# ELC102_-_Green_Digits.net
KiCad netlist of a schematic drawn in Altium Designer
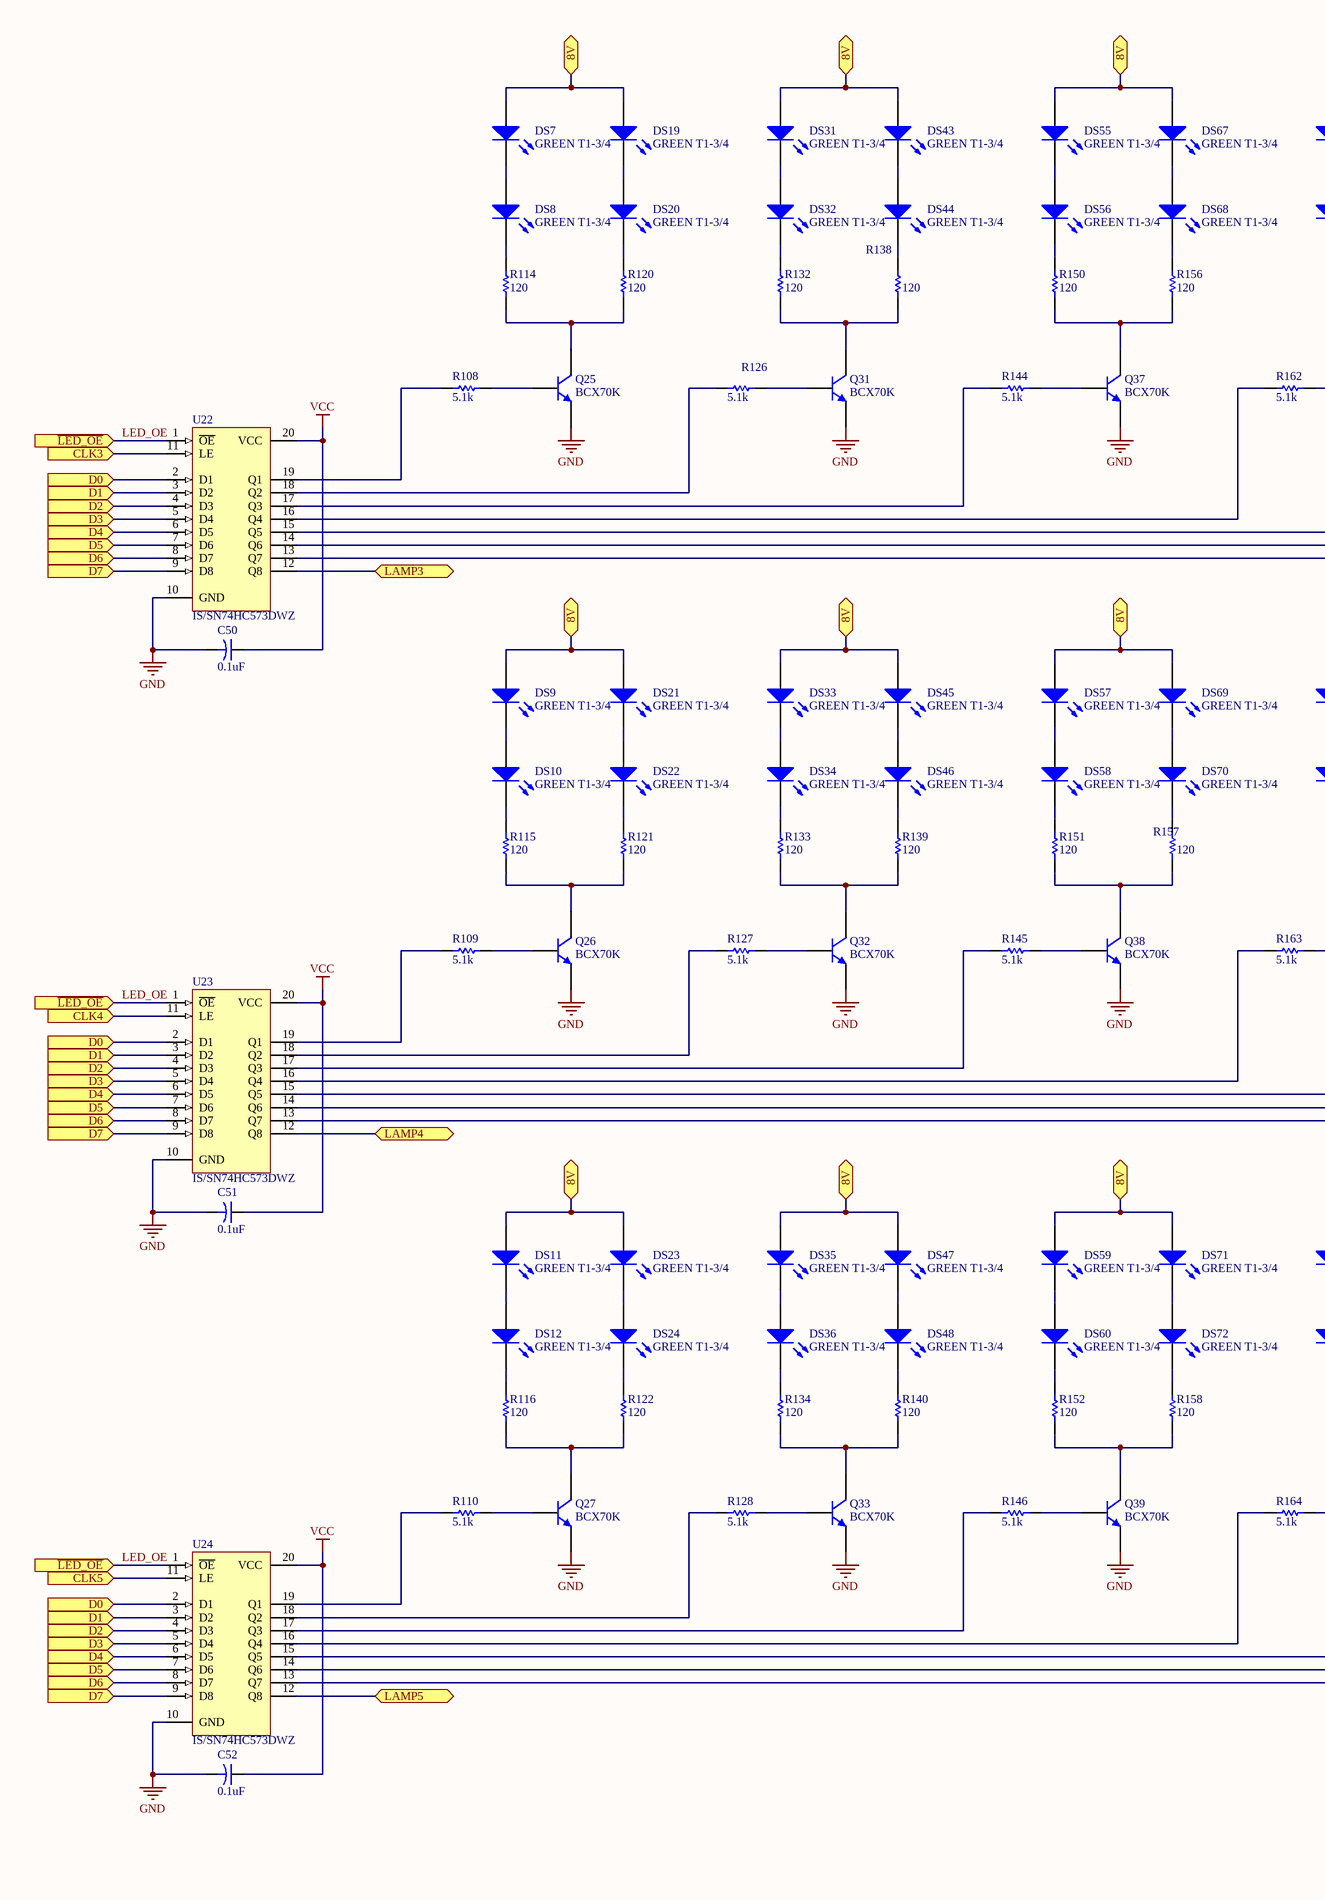
[diagram p0: ELC102 - Green Digits.SchDoc, left]
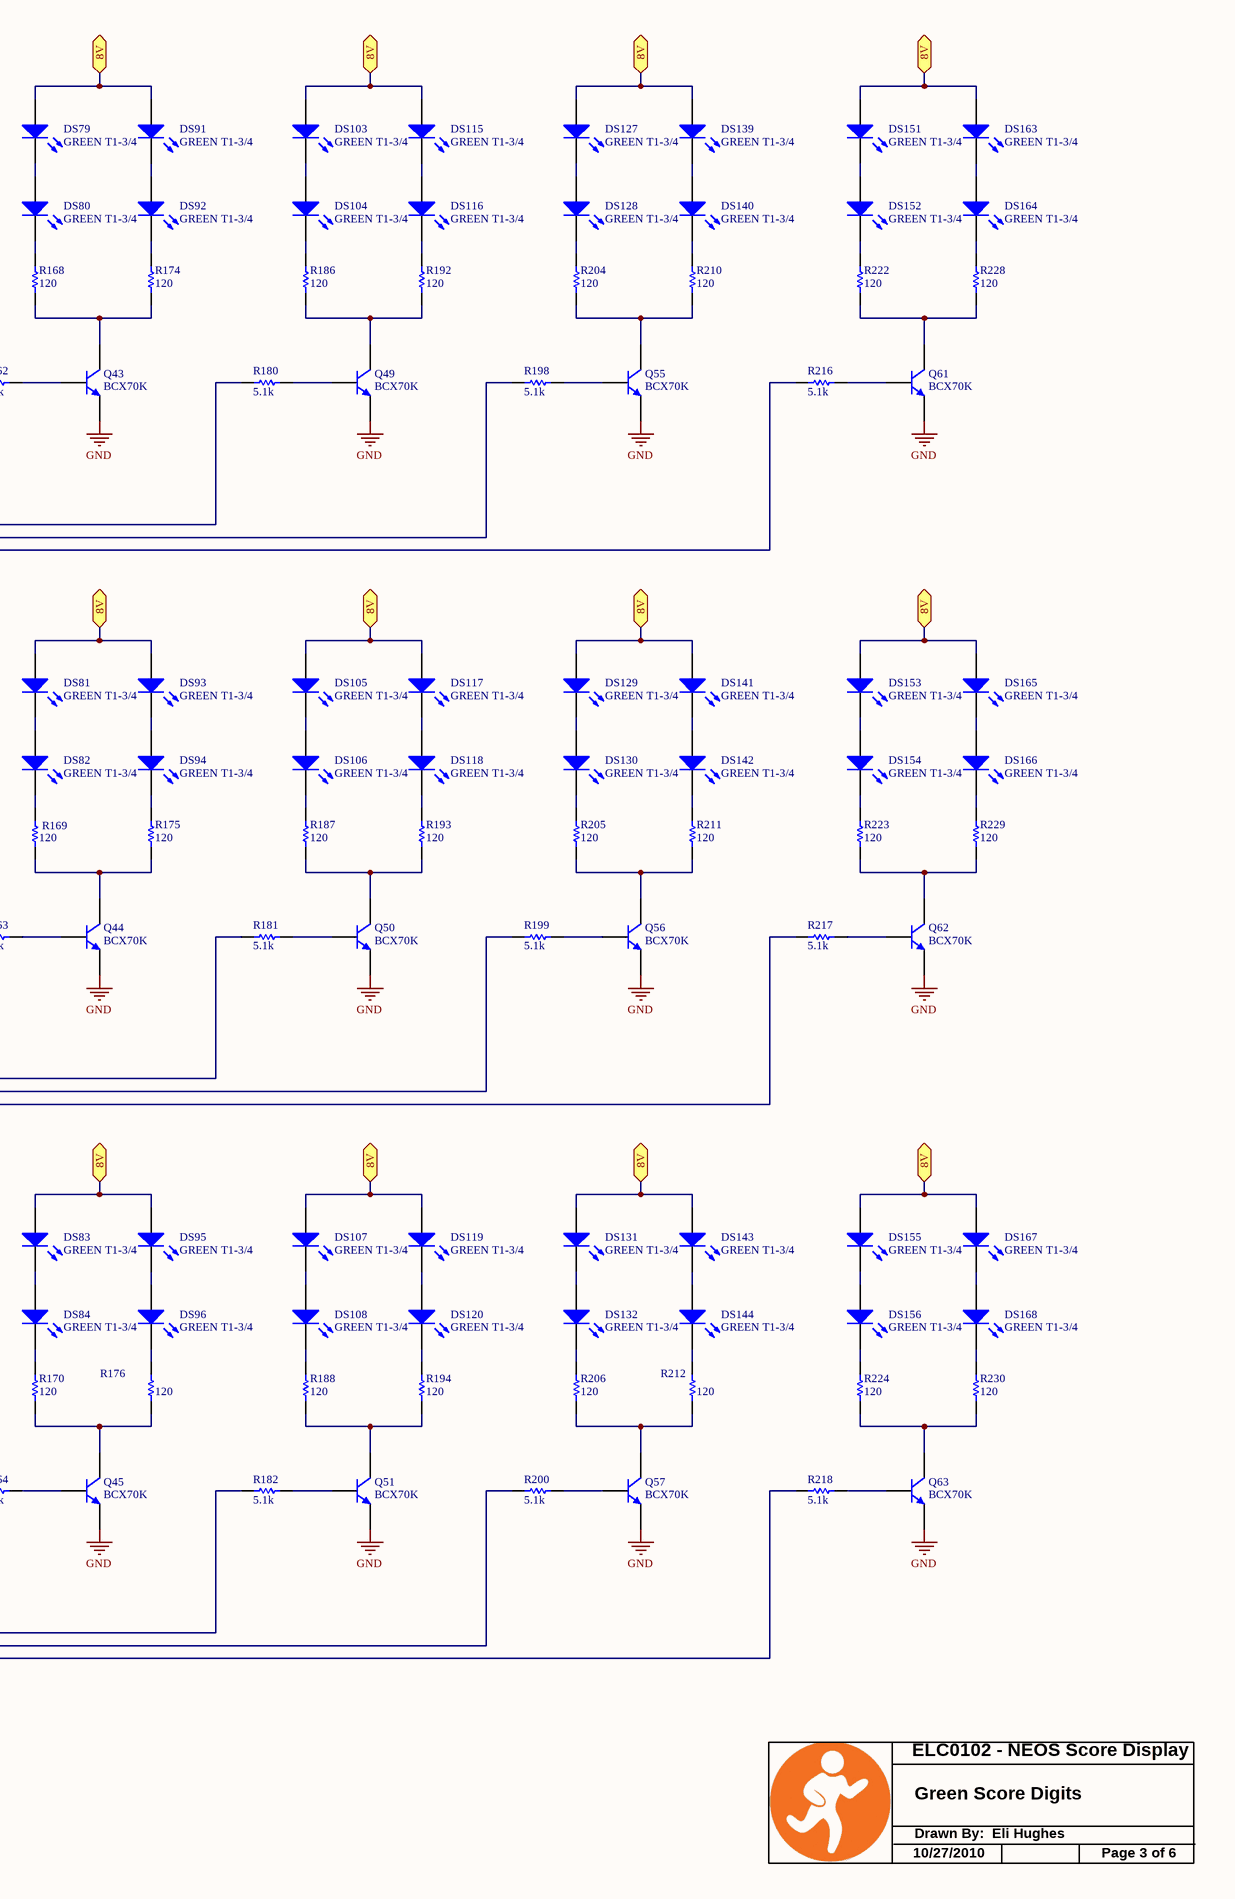
[diagram p1: ELC102 - Green Digits.SchDoc, right]

(export (version "E")
  (design (tool "Eeschema 10.0.6"))
  (components
    (comp (ref "C50")
      (value "0.1uF")
      (footprint "C0805")
      (description "CAP .10UF 50V CERAMIC X7R 0805")
      (fields
        (field (name "MANUFACTURER") "Kemet")
        (field (name "MANUFACTURER PART NUMBER") "C0805C104K5RACTU")
        (field (name "SOURCE") "Digikey")
      )
      (libsource (lib "ELC102 - Scoreboard") (part "CS/C0805C104K5RACK"))
    )
    (comp (ref "C51")
      (value "0.1uF")
      (footprint "C0805")
      (description "CAP .10UF 50V CERAMIC X7R 0805")
      (fields
        (field (name "MANUFACTURER") "Kemet")
        (field (name "MANUFACTURER PART NUMBER") "C0805C104K5RACTU")
        (field (name "SOURCE") "Digikey")
      )
      (libsource (lib "ELC102 - Scoreboard") (part "CS/C0805C104K5RACK"))
    )
    (comp (ref "C52")
      (value "0.1uF")
      (footprint "C0805")
      (description "CAP .10UF 50V CERAMIC X7R 0805")
      (fields
        (field (name "MANUFACTURER") "Kemet")
        (field (name "MANUFACTURER PART NUMBER") "C0805C104K5RACTU")
        (field (name "SOURCE") "Digikey")
      )
      (libsource (lib "ELC102 - Scoreboard") (part "CS/C0805C104K5RACK"))
    )
    (comp (ref "DS7")
      (value "GREEN T1-3/4")
      (footprint "LED T1-3/4 Flush")
      (description "Optek LED Green/Clear High Brightness T1-3/4")
      (fields
        (field (name "MANUFACTURER") "OPTEK")
        (field (name "MANUFACTURER PART NUMBER") "OVLFG3C7")
        (field (name "SOURCE") "Digikey")
      )
      (libsource (lib "ScoreBoard") (part "LGCOVLFG3C7Z"))
    )
    (comp (ref "DS8")
      (value "GREEN T1-3/4")
      (footprint "LED T1-3/4 Flush")
      (description "Optek LED Green/Clear High Brightness T1-3/4")
      (fields
        (field (name "MANUFACTURER") "OPTEK")
        (field (name "MANUFACTURER PART NUMBER") "OVLFG3C7")
        (field (name "SOURCE") "Digikey")
      )
      (libsource (lib "ScoreBoard") (part "LGCOVLFG3C7Z"))
    )
    (comp (ref "DS9")
      (value "GREEN T1-3/4")
      (footprint "LED T1-3/4 Flush")
      (description "Optek LED Green/Clear High Brightness T1-3/4")
      (fields
        (field (name "MANUFACTURER") "OPTEK")
        (field (name "MANUFACTURER PART NUMBER") "OVLFG3C7")
        (field (name "SOURCE") "Digikey")
      )
      (libsource (lib "ScoreBoard") (part "LGCOVLFG3C7Z"))
    )
    (comp (ref "DS10")
      (value "GREEN T1-3/4")
      (footprint "LED T1-3/4 Flush")
      (description "Optek LED Green/Clear High Brightness T1-3/4")
      (fields
        (field (name "MANUFACTURER") "OPTEK")
        (field (name "MANUFACTURER PART NUMBER") "OVLFG3C7")
        (field (name "SOURCE") "Digikey")
      )
      (libsource (lib "ScoreBoard") (part "LGCOVLFG3C7Z"))
    )
    (comp (ref "DS11")
      (value "GREEN T1-3/4")
      (footprint "LED T1-3/4 Flush")
      (description "Optek LED Green/Clear High Brightness T1-3/4")
      (fields
        (field (name "MANUFACTURER") "OPTEK")
        (field (name "MANUFACTURER PART NUMBER") "OVLFG3C7")
        (field (name "SOURCE") "Digikey")
      )
      (libsource (lib "ScoreBoard") (part "LGCOVLFG3C7Z"))
    )
    (comp (ref "DS12")
      (value "GREEN T1-3/4")
      (footprint "LED T1-3/4 Flush")
      (description "Optek LED Green/Clear High Brightness T1-3/4")
      (fields
        (field (name "MANUFACTURER") "OPTEK")
        (field (name "MANUFACTURER PART NUMBER") "OVLFG3C7")
        (field (name "SOURCE") "Digikey")
      )
      (libsource (lib "ScoreBoard") (part "LGCOVLFG3C7Z"))
    )
    (comp (ref "DS19")
      (value "GREEN T1-3/4")
      (footprint "LED T1-3/4 Flush")
      (description "Optek LED Green/Clear High Brightness T1-3/4")
      (fields
        (field (name "MANUFACTURER") "OPTEK")
        (field (name "MANUFACTURER PART NUMBER") "OVLFG3C7")
        (field (name "SOURCE") "Digikey")
      )
      (libsource (lib "ScoreBoard") (part "LGCOVLFG3C7Z"))
    )
    (comp (ref "DS20")
      (value "GREEN T1-3/4")
      (footprint "LED T1-3/4 Flush")
      (description "Optek LED Green/Clear High Brightness T1-3/4")
      (fields
        (field (name "MANUFACTURER") "OPTEK")
        (field (name "MANUFACTURER PART NUMBER") "OVLFG3C7")
        (field (name "SOURCE") "Digikey")
      )
      (libsource (lib "ScoreBoard") (part "LGCOVLFG3C7Z"))
    )
    (comp (ref "DS21")
      (value "GREEN T1-3/4")
      (footprint "LED T1-3/4 Flush")
      (description "Optek LED Green/Clear High Brightness T1-3/4")
      (fields
        (field (name "MANUFACTURER") "OPTEK")
        (field (name "MANUFACTURER PART NUMBER") "OVLFG3C7")
        (field (name "SOURCE") "Digikey")
      )
      (libsource (lib "ScoreBoard") (part "LGCOVLFG3C7Z"))
    )
    (comp (ref "DS22")
      (value "GREEN T1-3/4")
      (footprint "LED T1-3/4 Flush")
      (description "Optek LED Green/Clear High Brightness T1-3/4")
      (fields
        (field (name "MANUFACTURER") "OPTEK")
        (field (name "MANUFACTURER PART NUMBER") "OVLFG3C7")
        (field (name "SOURCE") "Digikey")
      )
      (libsource (lib "ScoreBoard") (part "LGCOVLFG3C7Z"))
    )
    (comp (ref "DS23")
      (value "GREEN T1-3/4")
      (footprint "LED T1-3/4 Flush")
      (description "Optek LED Green/Clear High Brightness T1-3/4")
      (fields
        (field (name "MANUFACTURER") "OPTEK")
        (field (name "MANUFACTURER PART NUMBER") "OVLFG3C7")
        (field (name "SOURCE") "Digikey")
      )
      (libsource (lib "ScoreBoard") (part "LGCOVLFG3C7Z"))
    )
    (comp (ref "DS24")
      (value "GREEN T1-3/4")
      (footprint "LED T1-3/4 Flush")
      (description "Optek LED Green/Clear High Brightness T1-3/4")
      (fields
        (field (name "MANUFACTURER") "OPTEK")
        (field (name "MANUFACTURER PART NUMBER") "OVLFG3C7")
        (field (name "SOURCE") "Digikey")
      )
      (libsource (lib "ScoreBoard") (part "LGCOVLFG3C7Z"))
    )
    (comp (ref "DS31")
      (value "GREEN T1-3/4")
      (footprint "LED T1-3/4 Flush")
      (description "Optek LED Green/Clear High Brightness T1-3/4")
      (fields
        (field (name "MANUFACTURER") "OPTEK")
        (field (name "MANUFACTURER PART NUMBER") "OVLFG3C7")
        (field (name "SOURCE") "Digikey")
      )
      (libsource (lib "ScoreBoard") (part "LGCOVLFG3C7Z"))
    )
    (comp (ref "DS32")
      (value "GREEN T1-3/4")
      (footprint "LED T1-3/4 Flush")
      (description "Optek LED Green/Clear High Brightness T1-3/4")
      (fields
        (field (name "MANUFACTURER") "OPTEK")
        (field (name "MANUFACTURER PART NUMBER") "OVLFG3C7")
        (field (name "SOURCE") "Digikey")
      )
      (libsource (lib "ScoreBoard") (part "LGCOVLFG3C7Z"))
    )
    (comp (ref "DS33")
      (value "GREEN T1-3/4")
      (footprint "LED T1-3/4 Flush")
      (description "Optek LED Green/Clear High Brightness T1-3/4")
      (fields
        (field (name "MANUFACTURER") "OPTEK")
        (field (name "MANUFACTURER PART NUMBER") "OVLFG3C7")
        (field (name "SOURCE") "Digikey")
      )
      (libsource (lib "ScoreBoard") (part "LGCOVLFG3C7Z"))
    )
    (comp (ref "DS34")
      (value "GREEN T1-3/4")
      (footprint "LED T1-3/4 Flush")
      (description "Optek LED Green/Clear High Brightness T1-3/4")
      (fields
        (field (name "MANUFACTURER") "OPTEK")
        (field (name "MANUFACTURER PART NUMBER") "OVLFG3C7")
        (field (name "SOURCE") "Digikey")
      )
      (libsource (lib "ScoreBoard") (part "LGCOVLFG3C7Z"))
    )
    (comp (ref "DS35")
      (value "GREEN T1-3/4")
      (footprint "LED T1-3/4 Flush")
      (description "Optek LED Green/Clear High Brightness T1-3/4")
      (fields
        (field (name "MANUFACTURER") "OPTEK")
        (field (name "MANUFACTURER PART NUMBER") "OVLFG3C7")
        (field (name "SOURCE") "Digikey")
      )
      (libsource (lib "ScoreBoard") (part "LGCOVLFG3C7Z"))
    )
    (comp (ref "DS36")
      (value "GREEN T1-3/4")
      (footprint "LED T1-3/4 Flush")
      (description "Optek LED Green/Clear High Brightness T1-3/4")
      (fields
        (field (name "MANUFACTURER") "OPTEK")
        (field (name "MANUFACTURER PART NUMBER") "OVLFG3C7")
        (field (name "SOURCE") "Digikey")
      )
      (libsource (lib "ScoreBoard") (part "LGCOVLFG3C7Z"))
    )
    (comp (ref "DS43")
      (value "GREEN T1-3/4")
      (footprint "LED T1-3/4 Flush")
      (description "Optek LED Green/Clear High Brightness T1-3/4")
      (fields
        (field (name "MANUFACTURER") "OPTEK")
        (field (name "MANUFACTURER PART NUMBER") "OVLFG3C7")
        (field (name "SOURCE") "Digikey")
      )
      (libsource (lib "ScoreBoard") (part "LGCOVLFG3C7Z"))
    )
    (comp (ref "DS44")
      (value "GREEN T1-3/4")
      (footprint "LED T1-3/4 Flush")
      (description "Optek LED Green/Clear High Brightness T1-3/4")
      (fields
        (field (name "MANUFACTURER") "OPTEK")
        (field (name "MANUFACTURER PART NUMBER") "OVLFG3C7")
        (field (name "SOURCE") "Digikey")
      )
      (libsource (lib "ScoreBoard") (part "LGCOVLFG3C7Z"))
    )
    (comp (ref "DS45")
      (value "GREEN T1-3/4")
      (footprint "LED T1-3/4 Flush")
      (description "Optek LED Green/Clear High Brightness T1-3/4")
      (fields
        (field (name "MANUFACTURER") "OPTEK")
        (field (name "MANUFACTURER PART NUMBER") "OVLFG3C7")
        (field (name "SOURCE") "Digikey")
      )
      (libsource (lib "ScoreBoard") (part "LGCOVLFG3C7Z"))
    )
    (comp (ref "DS46")
      (value "GREEN T1-3/4")
      (footprint "LED T1-3/4 Flush")
      (description "Optek LED Green/Clear High Brightness T1-3/4")
      (fields
        (field (name "MANUFACTURER") "OPTEK")
        (field (name "MANUFACTURER PART NUMBER") "OVLFG3C7")
        (field (name "SOURCE") "Digikey")
      )
      (libsource (lib "ScoreBoard") (part "LGCOVLFG3C7Z"))
    )
    (comp (ref "DS47")
      (value "GREEN T1-3/4")
      (footprint "LED T1-3/4 Flush")
      (description "Optek LED Green/Clear High Brightness T1-3/4")
      (fields
        (field (name "MANUFACTURER") "OPTEK")
        (field (name "MANUFACTURER PART NUMBER") "OVLFG3C7")
        (field (name "SOURCE") "Digikey")
      )
      (libsource (lib "ScoreBoard") (part "LGCOVLFG3C7Z"))
    )
    (comp (ref "DS48")
      (value "GREEN T1-3/4")
      (footprint "LED T1-3/4 Flush")
      (description "Optek LED Green/Clear High Brightness T1-3/4")
      (fields
        (field (name "MANUFACTURER") "OPTEK")
        (field (name "MANUFACTURER PART NUMBER") "OVLFG3C7")
        (field (name "SOURCE") "Digikey")
      )
      (libsource (lib "ScoreBoard") (part "LGCOVLFG3C7Z"))
    )
    (comp (ref "DS55")
      (value "GREEN T1-3/4")
      (footprint "LED T1-3/4 Flush")
      (description "Optek LED Green/Clear High Brightness T1-3/4")
      (fields
        (field (name "MANUFACTURER") "OPTEK")
        (field (name "MANUFACTURER PART NUMBER") "OVLFG3C7")
        (field (name "SOURCE") "Digikey")
      )
      (libsource (lib "ScoreBoard") (part "LGCOVLFG3C7Z"))
    )
    (comp (ref "DS56")
      (value "GREEN T1-3/4")
      (footprint "LED T1-3/4 Flush")
      (description "Optek LED Green/Clear High Brightness T1-3/4")
      (fields
        (field (name "MANUFACTURER") "OPTEK")
        (field (name "MANUFACTURER PART NUMBER") "OVLFG3C7")
        (field (name "SOURCE") "Digikey")
      )
      (libsource (lib "ScoreBoard") (part "LGCOVLFG3C7Z"))
    )
    (comp (ref "DS57")
      (value "GREEN T1-3/4")
      (footprint "LED T1-3/4 Flush")
      (description "Optek LED Green/Clear High Brightness T1-3/4")
      (fields
        (field (name "MANUFACTURER") "OPTEK")
        (field (name "MANUFACTURER PART NUMBER") "OVLFG3C7")
        (field (name "SOURCE") "Digikey")
      )
      (libsource (lib "ScoreBoard") (part "LGCOVLFG3C7Z"))
    )
    (comp (ref "DS58")
      (value "GREEN T1-3/4")
      (footprint "LED T1-3/4 Flush")
      (description "Optek LED Green/Clear High Brightness T1-3/4")
      (fields
        (field (name "MANUFACTURER") "OPTEK")
        (field (name "MANUFACTURER PART NUMBER") "OVLFG3C7")
        (field (name "SOURCE") "Digikey")
      )
      (libsource (lib "ScoreBoard") (part "LGCOVLFG3C7Z"))
    )
    (comp (ref "DS59")
      (value "GREEN T1-3/4")
      (footprint "LED T1-3/4 Flush")
      (description "Optek LED Green/Clear High Brightness T1-3/4")
      (fields
        (field (name "MANUFACTURER") "OPTEK")
        (field (name "MANUFACTURER PART NUMBER") "OVLFG3C7")
        (field (name "SOURCE") "Digikey")
      )
      (libsource (lib "ScoreBoard") (part "LGCOVLFG3C7Z"))
    )
    (comp (ref "DS60")
      (value "GREEN T1-3/4")
      (footprint "LED T1-3/4 Flush")
      (description "Optek LED Green/Clear High Brightness T1-3/4")
      (fields
        (field (name "MANUFACTURER") "OPTEK")
        (field (name "MANUFACTURER PART NUMBER") "OVLFG3C7")
        (field (name "SOURCE") "Digikey")
      )
      (libsource (lib "ScoreBoard") (part "LGCOVLFG3C7Z"))
    )
    (comp (ref "DS67")
      (value "GREEN T1-3/4")
      (footprint "LED T1-3/4 Flush")
      (description "Optek LED Green/Clear High Brightness T1-3/4")
      (fields
        (field (name "MANUFACTURER") "OPTEK")
        (field (name "MANUFACTURER PART NUMBER") "OVLFG3C7")
        (field (name "SOURCE") "Digikey")
      )
      (libsource (lib "ScoreBoard") (part "LGCOVLFG3C7Z"))
    )
    (comp (ref "DS68")
      (value "GREEN T1-3/4")
      (footprint "LED T1-3/4 Flush")
      (description "Optek LED Green/Clear High Brightness T1-3/4")
      (fields
        (field (name "MANUFACTURER") "OPTEK")
        (field (name "MANUFACTURER PART NUMBER") "OVLFG3C7")
        (field (name "SOURCE") "Digikey")
      )
      (libsource (lib "ScoreBoard") (part "LGCOVLFG3C7Z"))
    )
    (comp (ref "DS69")
      (value "GREEN T1-3/4")
      (footprint "LED T1-3/4 Flush")
      (description "Optek LED Green/Clear High Brightness T1-3/4")
      (fields
        (field (name "MANUFACTURER") "OPTEK")
        (field (name "MANUFACTURER PART NUMBER") "OVLFG3C7")
        (field (name "SOURCE") "Digikey")
      )
      (libsource (lib "ScoreBoard") (part "LGCOVLFG3C7Z"))
    )
    (comp (ref "DS70")
      (value "GREEN T1-3/4")
      (footprint "LED T1-3/4 Flush")
      (description "Optek LED Green/Clear High Brightness T1-3/4")
      (fields
        (field (name "MANUFACTURER") "OPTEK")
        (field (name "MANUFACTURER PART NUMBER") "OVLFG3C7")
        (field (name "SOURCE") "Digikey")
      )
      (libsource (lib "ScoreBoard") (part "LGCOVLFG3C7Z"))
    )
    (comp (ref "DS71")
      (value "GREEN T1-3/4")
      (footprint "LED T1-3/4 Flush")
      (description "Optek LED Green/Clear High Brightness T1-3/4")
      (fields
        (field (name "MANUFACTURER") "OPTEK")
        (field (name "MANUFACTURER PART NUMBER") "OVLFG3C7")
        (field (name "SOURCE") "Digikey")
      )
      (libsource (lib "ScoreBoard") (part "LGCOVLFG3C7Z"))
    )
    (comp (ref "DS72")
      (value "GREEN T1-3/4")
      (footprint "LED T1-3/4 Flush")
      (description "Optek LED Green/Clear High Brightness T1-3/4")
      (fields
        (field (name "MANUFACTURER") "OPTEK")
        (field (name "MANUFACTURER PART NUMBER") "OVLFG3C7")
        (field (name "SOURCE") "Digikey")
      )
      (libsource (lib "ScoreBoard") (part "LGCOVLFG3C7Z"))
    )
    (comp (ref "DS79")
      (value "GREEN T1-3/4")
      (footprint "LED T1-3/4 Flush")
      (description "Optek LED Green/Clear High Brightness T1-3/4")
      (fields
        (field (name "MANUFACTURER") "OPTEK")
        (field (name "MANUFACTURER PART NUMBER") "OVLFG3C7")
        (field (name "SOURCE") "Digikey")
      )
      (libsource (lib "ScoreBoard") (part "LGCOVLFG3C7Z"))
    )
    (comp (ref "DS80")
      (value "GREEN T1-3/4")
      (footprint "LED T1-3/4 Flush")
      (description "Optek LED Green/Clear High Brightness T1-3/4")
      (fields
        (field (name "MANUFACTURER") "OPTEK")
        (field (name "MANUFACTURER PART NUMBER") "OVLFG3C7")
        (field (name "SOURCE") "Digikey")
      )
      (libsource (lib "ScoreBoard") (part "LGCOVLFG3C7Z"))
    )
    (comp (ref "DS81")
      (value "GREEN T1-3/4")
      (footprint "LED T1-3/4 Flush")
      (description "Optek LED Green/Clear High Brightness T1-3/4")
      (fields
        (field (name "MANUFACTURER") "OPTEK")
        (field (name "MANUFACTURER PART NUMBER") "OVLFG3C7")
        (field (name "SOURCE") "Digikey")
      )
      (libsource (lib "ScoreBoard") (part "LGCOVLFG3C7Z"))
    )
    (comp (ref "DS82")
      (value "GREEN T1-3/4")
      (footprint "LED T1-3/4 Flush")
      (description "Optek LED Green/Clear High Brightness T1-3/4")
      (fields
        (field (name "MANUFACTURER") "OPTEK")
        (field (name "MANUFACTURER PART NUMBER") "OVLFG3C7")
        (field (name "SOURCE") "Digikey")
      )
      (libsource (lib "ScoreBoard") (part "LGCOVLFG3C7Z"))
    )
    (comp (ref "DS83")
      (value "GREEN T1-3/4")
      (footprint "LED T1-3/4 Flush")
      (description "Optek LED Green/Clear High Brightness T1-3/4")
      (fields
        (field (name "MANUFACTURER") "OPTEK")
        (field (name "MANUFACTURER PART NUMBER") "OVLFG3C7")
        (field (name "SOURCE") "Digikey")
      )
      (libsource (lib "ScoreBoard") (part "LGCOVLFG3C7Z"))
    )
    (comp (ref "DS84")
      (value "GREEN T1-3/4")
      (footprint "LED T1-3/4 Flush")
      (description "Optek LED Green/Clear High Brightness T1-3/4")
      (fields
        (field (name "MANUFACTURER") "OPTEK")
        (field (name "MANUFACTURER PART NUMBER") "OVLFG3C7")
        (field (name "SOURCE") "Digikey")
      )
      (libsource (lib "ScoreBoard") (part "LGCOVLFG3C7Z"))
    )
    (comp (ref "DS91")
      (value "GREEN T1-3/4")
      (footprint "LED T1-3/4 Flush")
      (description "Optek LED Green/Clear High Brightness T1-3/4")
      (fields
        (field (name "MANUFACTURER") "OPTEK")
        (field (name "MANUFACTURER PART NUMBER") "OVLFG3C7")
        (field (name "SOURCE") "Digikey")
      )
      (libsource (lib "ScoreBoard") (part "LGCOVLFG3C7Z"))
    )
    (comp (ref "DS92")
      (value "GREEN T1-3/4")
      (footprint "LED T1-3/4 Flush")
      (description "Optek LED Green/Clear High Brightness T1-3/4")
      (fields
        (field (name "MANUFACTURER") "OPTEK")
        (field (name "MANUFACTURER PART NUMBER") "OVLFG3C7")
        (field (name "SOURCE") "Digikey")
      )
      (libsource (lib "ScoreBoard") (part "LGCOVLFG3C7Z"))
    )
    (comp (ref "DS93")
      (value "GREEN T1-3/4")
      (footprint "LED T1-3/4 Flush")
      (description "Optek LED Green/Clear High Brightness T1-3/4")
      (fields
        (field (name "MANUFACTURER") "OPTEK")
        (field (name "MANUFACTURER PART NUMBER") "OVLFG3C7")
        (field (name "SOURCE") "Digikey")
      )
      (libsource (lib "ScoreBoard") (part "LGCOVLFG3C7Z"))
    )
    (comp (ref "DS94")
      (value "GREEN T1-3/4")
      (footprint "LED T1-3/4 Flush")
      (description "Optek LED Green/Clear High Brightness T1-3/4")
      (fields
        (field (name "MANUFACTURER") "OPTEK")
        (field (name "MANUFACTURER PART NUMBER") "OVLFG3C7")
        (field (name "SOURCE") "Digikey")
      )
      (libsource (lib "ScoreBoard") (part "LGCOVLFG3C7Z"))
    )
    (comp (ref "DS95")
      (value "GREEN T1-3/4")
      (footprint "LED T1-3/4 Flush")
      (description "Optek LED Green/Clear High Brightness T1-3/4")
      (fields
        (field (name "MANUFACTURER") "OPTEK")
        (field (name "MANUFACTURER PART NUMBER") "OVLFG3C7")
        (field (name "SOURCE") "Digikey")
      )
      (libsource (lib "ScoreBoard") (part "LGCOVLFG3C7Z"))
    )
    (comp (ref "DS96")
      (value "GREEN T1-3/4")
      (footprint "LED T1-3/4 Flush")
      (description "Optek LED Green/Clear High Brightness T1-3/4")
      (fields
        (field (name "MANUFACTURER") "OPTEK")
        (field (name "MANUFACTURER PART NUMBER") "OVLFG3C7")
        (field (name "SOURCE") "Digikey")
      )
      (libsource (lib "ScoreBoard") (part "LGCOVLFG3C7Z"))
    )
    (comp (ref "DS103")
      (value "GREEN T1-3/4")
      (footprint "LED T1-3/4 Flush")
      (description "Optek LED Green/Clear High Brightness T1-3/4")
      (fields
        (field (name "MANUFACTURER") "OPTEK")
        (field (name "MANUFACTURER PART NUMBER") "OVLFG3C7")
        (field (name "SOURCE") "Digikey")
      )
      (libsource (lib "ScoreBoard") (part "LGCOVLFG3C7Z"))
    )
    (comp (ref "DS104")
      (value "GREEN T1-3/4")
      (footprint "LED T1-3/4 Flush")
      (description "Optek LED Green/Clear High Brightness T1-3/4")
      (fields
        (field (name "MANUFACTURER") "OPTEK")
        (field (name "MANUFACTURER PART NUMBER") "OVLFG3C7")
        (field (name "SOURCE") "Digikey")
      )
      (libsource (lib "ScoreBoard") (part "LGCOVLFG3C7Z"))
    )
    (comp (ref "DS105")
      (value "GREEN T1-3/4")
      (footprint "LED T1-3/4 Flush")
      (description "Optek LED Green/Clear High Brightness T1-3/4")
      (fields
        (field (name "MANUFACTURER") "OPTEK")
        (field (name "MANUFACTURER PART NUMBER") "OVLFG3C7")
        (field (name "SOURCE") "Digikey")
      )
      (libsource (lib "ScoreBoard") (part "LGCOVLFG3C7Z"))
    )
    (comp (ref "DS106")
      (value "GREEN T1-3/4")
      (footprint "LED T1-3/4 Flush")
      (description "Optek LED Green/Clear High Brightness T1-3/4")
      (fields
        (field (name "MANUFACTURER") "OPTEK")
        (field (name "MANUFACTURER PART NUMBER") "OVLFG3C7")
        (field (name "SOURCE") "Digikey")
      )
      (libsource (lib "ScoreBoard") (part "LGCOVLFG3C7Z"))
    )
    (comp (ref "DS107")
      (value "GREEN T1-3/4")
      (footprint "LED T1-3/4 Flush")
      (description "Optek LED Green/Clear High Brightness T1-3/4")
      (fields
        (field (name "MANUFACTURER") "OPTEK")
        (field (name "MANUFACTURER PART NUMBER") "OVLFG3C7")
        (field (name "SOURCE") "Digikey")
      )
      (libsource (lib "ScoreBoard") (part "LGCOVLFG3C7Z"))
    )
    (comp (ref "DS108")
      (value "GREEN T1-3/4")
      (footprint "LED T1-3/4 Flush")
      (description "Optek LED Green/Clear High Brightness T1-3/4")
      (fields
        (field (name "MANUFACTURER") "OPTEK")
        (field (name "MANUFACTURER PART NUMBER") "OVLFG3C7")
        (field (name "SOURCE") "Digikey")
      )
      (libsource (lib "ScoreBoard") (part "LGCOVLFG3C7Z"))
    )
    (comp (ref "DS115")
      (value "GREEN T1-3/4")
      (footprint "LED T1-3/4 Flush")
      (description "Optek LED Green/Clear High Brightness T1-3/4")
      (fields
        (field (name "MANUFACTURER") "OPTEK")
        (field (name "MANUFACTURER PART NUMBER") "OVLFG3C7")
        (field (name "SOURCE") "Digikey")
      )
      (libsource (lib "ScoreBoard") (part "LGCOVLFG3C7Z"))
    )
    (comp (ref "DS116")
      (value "GREEN T1-3/4")
      (footprint "LED T1-3/4 Flush")
      (description "Optek LED Green/Clear High Brightness T1-3/4")
      (fields
        (field (name "MANUFACTURER") "OPTEK")
        (field (name "MANUFACTURER PART NUMBER") "OVLFG3C7")
        (field (name "SOURCE") "Digikey")
      )
      (libsource (lib "ScoreBoard") (part "LGCOVLFG3C7Z"))
    )
    (comp (ref "DS117")
      (value "GREEN T1-3/4")
      (footprint "LED T1-3/4 Flush")
      (description "Optek LED Green/Clear High Brightness T1-3/4")
      (fields
        (field (name "MANUFACTURER") "OPTEK")
        (field (name "MANUFACTURER PART NUMBER") "OVLFG3C7")
        (field (name "SOURCE") "Digikey")
      )
      (libsource (lib "ScoreBoard") (part "LGCOVLFG3C7Z"))
    )
    (comp (ref "DS118")
      (value "GREEN T1-3/4")
      (footprint "LED T1-3/4 Flush")
      (description "Optek LED Green/Clear High Brightness T1-3/4")
      (fields
        (field (name "MANUFACTURER") "OPTEK")
        (field (name "MANUFACTURER PART NUMBER") "OVLFG3C7")
        (field (name "SOURCE") "Digikey")
      )
      (libsource (lib "ScoreBoard") (part "LGCOVLFG3C7Z"))
    )
    (comp (ref "DS119")
      (value "GREEN T1-3/4")
      (footprint "LED T1-3/4 Flush")
      (description "Optek LED Green/Clear High Brightness T1-3/4")
      (fields
        (field (name "MANUFACTURER") "OPTEK")
        (field (name "MANUFACTURER PART NUMBER") "OVLFG3C7")
        (field (name "SOURCE") "Digikey")
      )
      (libsource (lib "ScoreBoard") (part "LGCOVLFG3C7Z"))
    )
    (comp (ref "DS120")
      (value "GREEN T1-3/4")
      (footprint "LED T1-3/4 Flush")
      (description "Optek LED Green/Clear High Brightness T1-3/4")
      (fields
        (field (name "MANUFACTURER") "OPTEK")
        (field (name "MANUFACTURER PART NUMBER") "OVLFG3C7")
        (field (name "SOURCE") "Digikey")
      )
      (libsource (lib "ScoreBoard") (part "LGCOVLFG3C7Z"))
    )
    (comp (ref "DS127")
      (value "GREEN T1-3/4")
      (footprint "LED T1-3/4 Flush")
      (description "Optek LED Green/Clear High Brightness T1-3/4")
      (fields
        (field (name "MANUFACTURER") "OPTEK")
        (field (name "MANUFACTURER PART NUMBER") "OVLFG3C7")
        (field (name "SOURCE") "Digikey")
      )
      (libsource (lib "ScoreBoard") (part "LGCOVLFG3C7Z"))
    )
    (comp (ref "DS128")
      (value "GREEN T1-3/4")
      (footprint "LED T1-3/4 Flush")
      (description "Optek LED Green/Clear High Brightness T1-3/4")
      (fields
        (field (name "MANUFACTURER") "OPTEK")
        (field (name "MANUFACTURER PART NUMBER") "OVLFG3C7")
        (field (name "SOURCE") "Digikey")
      )
      (libsource (lib "ScoreBoard") (part "LGCOVLFG3C7Z"))
    )
    (comp (ref "DS129")
      (value "GREEN T1-3/4")
      (footprint "LED T1-3/4 Flush")
      (description "Optek LED Green/Clear High Brightness T1-3/4")
      (fields
        (field (name "MANUFACTURER") "OPTEK")
        (field (name "MANUFACTURER PART NUMBER") "OVLFG3C7")
        (field (name "SOURCE") "Digikey")
      )
      (libsource (lib "ScoreBoard") (part "LGCOVLFG3C7Z"))
    )
    (comp (ref "DS130")
      (value "GREEN T1-3/4")
      (footprint "LED T1-3/4 Flush")
      (description "Optek LED Green/Clear High Brightness T1-3/4")
      (fields
        (field (name "MANUFACTURER") "OPTEK")
        (field (name "MANUFACTURER PART NUMBER") "OVLFG3C7")
        (field (name "SOURCE") "Digikey")
      )
      (libsource (lib "ScoreBoard") (part "LGCOVLFG3C7Z"))
    )
    (comp (ref "DS131")
      (value "GREEN T1-3/4")
      (footprint "LED T1-3/4 Flush")
      (description "Optek LED Green/Clear High Brightness T1-3/4")
      (fields
        (field (name "MANUFACTURER") "OPTEK")
        (field (name "MANUFACTURER PART NUMBER") "OVLFG3C7")
        (field (name "SOURCE") "Digikey")
      )
      (libsource (lib "ScoreBoard") (part "LGCOVLFG3C7Z"))
    )
    (comp (ref "DS132")
      (value "GREEN T1-3/4")
      (footprint "LED T1-3/4 Flush")
      (description "Optek LED Green/Clear High Brightness T1-3/4")
      (fields
        (field (name "MANUFACTURER") "OPTEK")
        (field (name "MANUFACTURER PART NUMBER") "OVLFG3C7")
        (field (name "SOURCE") "Digikey")
      )
      (libsource (lib "ScoreBoard") (part "LGCOVLFG3C7Z"))
    )
    (comp (ref "DS139")
      (value "GREEN T1-3/4")
      (footprint "LED T1-3/4 Flush")
      (description "Optek LED Green/Clear High Brightness T1-3/4")
      (fields
        (field (name "MANUFACTURER") "OPTEK")
        (field (name "MANUFACTURER PART NUMBER") "OVLFG3C7")
        (field (name "SOURCE") "Digikey")
      )
      (libsource (lib "ScoreBoard") (part "LGCOVLFG3C7Z"))
    )
    (comp (ref "DS140")
      (value "GREEN T1-3/4")
      (footprint "LED T1-3/4 Flush")
      (description "Optek LED Green/Clear High Brightness T1-3/4")
      (fields
        (field (name "MANUFACTURER") "OPTEK")
        (field (name "MANUFACTURER PART NUMBER") "OVLFG3C7")
        (field (name "SOURCE") "Digikey")
      )
      (libsource (lib "ScoreBoard") (part "LGCOVLFG3C7Z"))
    )
    (comp (ref "DS141")
      (value "GREEN T1-3/4")
      (footprint "LED T1-3/4 Flush")
      (description "Optek LED Green/Clear High Brightness T1-3/4")
      (fields
        (field (name "MANUFACTURER") "OPTEK")
        (field (name "MANUFACTURER PART NUMBER") "OVLFG3C7")
        (field (name "SOURCE") "Digikey")
      )
      (libsource (lib "ScoreBoard") (part "LGCOVLFG3C7Z"))
    )
    (comp (ref "DS142")
      (value "GREEN T1-3/4")
      (footprint "LED T1-3/4 Flush")
      (description "Optek LED Green/Clear High Brightness T1-3/4")
      (fields
        (field (name "MANUFACTURER") "OPTEK")
        (field (name "MANUFACTURER PART NUMBER") "OVLFG3C7")
        (field (name "SOURCE") "Digikey")
      )
      (libsource (lib "ScoreBoard") (part "LGCOVLFG3C7Z"))
    )
    (comp (ref "DS143")
      (value "GREEN T1-3/4")
      (footprint "LED T1-3/4 Flush")
      (description "Optek LED Green/Clear High Brightness T1-3/4")
      (fields
        (field (name "MANUFACTURER") "OPTEK")
        (field (name "MANUFACTURER PART NUMBER") "OVLFG3C7")
        (field (name "SOURCE") "Digikey")
      )
      (libsource (lib "ScoreBoard") (part "LGCOVLFG3C7Z"))
    )
    (comp (ref "DS144")
      (value "GREEN T1-3/4")
      (footprint "LED T1-3/4 Flush")
      (description "Optek LED Green/Clear High Brightness T1-3/4")
      (fields
        (field (name "MANUFACTURER") "OPTEK")
        (field (name "MANUFACTURER PART NUMBER") "OVLFG3C7")
        (field (name "SOURCE") "Digikey")
      )
      (libsource (lib "ScoreBoard") (part "LGCOVLFG3C7Z"))
    )
    (comp (ref "DS151")
      (value "GREEN T1-3/4")
      (footprint "LED T1-3/4 Flush")
      (description "Optek LED Green/Clear High Brightness T1-3/4")
      (fields
        (field (name "MANUFACTURER") "OPTEK")
        (field (name "MANUFACTURER PART NUMBER") "OVLFG3C7")
        (field (name "SOURCE") "Digikey")
      )
      (libsource (lib "ScoreBoard") (part "LGCOVLFG3C7Z"))
    )
    (comp (ref "DS152")
      (value "GREEN T1-3/4")
      (footprint "LED T1-3/4 Flush")
      (description "Optek LED Green/Clear High Brightness T1-3/4")
      (fields
        (field (name "MANUFACTURER") "OPTEK")
        (field (name "MANUFACTURER PART NUMBER") "OVLFG3C7")
        (field (name "SOURCE") "Digikey")
      )
      (libsource (lib "ScoreBoard") (part "LGCOVLFG3C7Z"))
    )
    (comp (ref "DS153")
      (value "GREEN T1-3/4")
      (footprint "LED T1-3/4 Flush")
      (description "Optek LED Green/Clear High Brightness T1-3/4")
      (fields
        (field (name "MANUFACTURER") "OPTEK")
        (field (name "MANUFACTURER PART NUMBER") "OVLFG3C7")
        (field (name "SOURCE") "Digikey")
      )
      (libsource (lib "ScoreBoard") (part "LGCOVLFG3C7Z"))
    )
    (comp (ref "DS154")
      (value "GREEN T1-3/4")
      (footprint "LED T1-3/4 Flush")
      (description "Optek LED Green/Clear High Brightness T1-3/4")
      (fields
        (field (name "MANUFACTURER") "OPTEK")
        (field (name "MANUFACTURER PART NUMBER") "OVLFG3C7")
        (field (name "SOURCE") "Digikey")
      )
      (libsource (lib "ScoreBoard") (part "LGCOVLFG3C7Z"))
    )
    (comp (ref "DS155")
      (value "GREEN T1-3/4")
      (footprint "LED T1-3/4 Flush")
      (description "Optek LED Green/Clear High Brightness T1-3/4")
      (fields
        (field (name "MANUFACTURER") "OPTEK")
        (field (name "MANUFACTURER PART NUMBER") "OVLFG3C7")
        (field (name "SOURCE") "Digikey")
      )
      (libsource (lib "ScoreBoard") (part "LGCOVLFG3C7Z"))
    )
    (comp (ref "DS156")
      (value "GREEN T1-3/4")
      (footprint "LED T1-3/4 Flush")
      (description "Optek LED Green/Clear High Brightness T1-3/4")
      (fields
        (field (name "MANUFACTURER") "OPTEK")
        (field (name "MANUFACTURER PART NUMBER") "OVLFG3C7")
        (field (name "SOURCE") "Digikey")
      )
      (libsource (lib "ScoreBoard") (part "LGCOVLFG3C7Z"))
    )
    (comp (ref "DS163")
      (value "GREEN T1-3/4")
      (footprint "LED T1-3/4 Flush")
      (description "Optek LED Green/Clear High Brightness T1-3/4")
      (fields
        (field (name "MANUFACTURER") "OPTEK")
        (field (name "MANUFACTURER PART NUMBER") "OVLFG3C7")
        (field (name "SOURCE") "Digikey")
      )
      (libsource (lib "ScoreBoard") (part "LGCOVLFG3C7Z"))
    )
    (comp (ref "DS164")
      (value "GREEN T1-3/4")
      (footprint "LED T1-3/4 Flush")
      (description "Optek LED Green/Clear High Brightness T1-3/4")
      (fields
        (field (name "MANUFACTURER") "OPTEK")
        (field (name "MANUFACTURER PART NUMBER") "OVLFG3C7")
        (field (name "SOURCE") "Digikey")
      )
      (libsource (lib "ScoreBoard") (part "LGCOVLFG3C7Z"))
    )
    (comp (ref "DS165")
      (value "GREEN T1-3/4")
      (footprint "LED T1-3/4 Flush")
      (description "Optek LED Green/Clear High Brightness T1-3/4")
      (fields
        (field (name "MANUFACTURER") "OPTEK")
        (field (name "MANUFACTURER PART NUMBER") "OVLFG3C7")
        (field (name "SOURCE") "Digikey")
      )
      (libsource (lib "ScoreBoard") (part "LGCOVLFG3C7Z"))
    )
    (comp (ref "DS166")
      (value "GREEN T1-3/4")
      (footprint "LED T1-3/4 Flush")
      (description "Optek LED Green/Clear High Brightness T1-3/4")
      (fields
        (field (name "MANUFACTURER") "OPTEK")
        (field (name "MANUFACTURER PART NUMBER") "OVLFG3C7")
        (field (name "SOURCE") "Digikey")
      )
      (libsource (lib "ScoreBoard") (part "LGCOVLFG3C7Z"))
    )
    (comp (ref "DS167")
      (value "GREEN T1-3/4")
      (footprint "LED T1-3/4 Flush")
      (description "Optek LED Green/Clear High Brightness T1-3/4")
      (fields
        (field (name "MANUFACTURER") "OPTEK")
        (field (name "MANUFACTURER PART NUMBER") "OVLFG3C7")
        (field (name "SOURCE") "Digikey")
      )
      (libsource (lib "ScoreBoard") (part "LGCOVLFG3C7Z"))
    )
    (comp (ref "DS168")
      (value "GREEN T1-3/4")
      (footprint "LED T1-3/4 Flush")
      (description "Optek LED Green/Clear High Brightness T1-3/4")
      (fields
        (field (name "MANUFACTURER") "OPTEK")
        (field (name "MANUFACTURER PART NUMBER") "OVLFG3C7")
        (field (name "SOURCE") "Digikey")
      )
      (libsource (lib "ScoreBoard") (part "LGCOVLFG3C7Z"))
    )
    (comp (ref "Q25")
      (value "BCX70K")
      (footprint "SOT23")
      (description "TRANS NPN AF 45V SOT-23")
      (fields (field (name "MANUFACTURER") "Fairchild Semiconductor") (field (name "SOURCE") "Digikey"))
      (libsource (lib "ScoreBoard") (part "QS/BCX70K00Z"))
    )
    (comp (ref "Q26")
      (value "BCX70K")
      (footprint "SOT23")
      (description "TRANS NPN AF 45V SOT-23")
      (fields (field (name "MANUFACTURER") "Fairchild Semiconductor") (field (name "SOURCE") "Digikey"))
      (libsource (lib "ScoreBoard") (part "QS/BCX70K00Z"))
    )
    (comp (ref "Q27")
      (value "BCX70K")
      (footprint "SOT23")
      (description "TRANS NPN AF 45V SOT-23")
      (fields (field (name "MANUFACTURER") "Fairchild Semiconductor") (field (name "SOURCE") "Digikey"))
      (libsource (lib "ScoreBoard") (part "QS/BCX70K00Z"))
    )
    (comp (ref "Q31")
      (value "BCX70K")
      (footprint "SOT23")
      (description "TRANS NPN AF 45V SOT-23")
      (fields (field (name "MANUFACTURER") "Fairchild Semiconductor") (field (name "SOURCE") "Digikey"))
      (libsource (lib "ScoreBoard") (part "QS/BCX70K00Z"))
    )
    (comp (ref "Q32")
      (value "BCX70K")
      (footprint "SOT23")
      (description "TRANS NPN AF 45V SOT-23")
      (fields (field (name "MANUFACTURER") "Fairchild Semiconductor") (field (name "SOURCE") "Digikey"))
      (libsource (lib "ScoreBoard") (part "QS/BCX70K00Z"))
    )
    (comp (ref "Q33")
      (value "BCX70K")
      (footprint "SOT23")
      (description "TRANS NPN AF 45V SOT-23")
      (fields (field (name "MANUFACTURER") "Fairchild Semiconductor") (field (name "SOURCE") "Digikey"))
      (libsource (lib "ScoreBoard") (part "QS/BCX70K00Z"))
    )
    (comp (ref "Q37")
      (value "BCX70K")
      (footprint "SOT23")
      (description "TRANS NPN AF 45V SOT-23")
      (fields (field (name "MANUFACTURER") "Fairchild Semiconductor") (field (name "SOURCE") "Digikey"))
      (libsource (lib "ScoreBoard") (part "QS/BCX70K00Z"))
    )
    (comp (ref "Q38")
      (value "BCX70K")
      (footprint "SOT23")
      (description "TRANS NPN AF 45V SOT-23")
      (fields (field (name "MANUFACTURER") "Fairchild Semiconductor") (field (name "SOURCE") "Digikey"))
      (libsource (lib "ScoreBoard") (part "QS/BCX70K00Z"))
    )
    (comp (ref "Q39")
      (value "BCX70K")
      (footprint "SOT23")
      (description "TRANS NPN AF 45V SOT-23")
      (fields (field (name "MANUFACTURER") "Fairchild Semiconductor") (field (name "SOURCE") "Digikey"))
      (libsource (lib "ScoreBoard") (part "QS/BCX70K00Z"))
    )
    (comp (ref "Q43")
      (value "BCX70K")
      (footprint "SOT23")
      (description "TRANS NPN AF 45V SOT-23")
      (fields (field (name "MANUFACTURER") "Fairchild Semiconductor") (field (name "SOURCE") "Digikey"))
      (libsource (lib "ScoreBoard") (part "QS/BCX70K00Z"))
    )
    (comp (ref "Q44")
      (value "BCX70K")
      (footprint "SOT23")
      (description "TRANS NPN AF 45V SOT-23")
      (fields (field (name "MANUFACTURER") "Fairchild Semiconductor") (field (name "SOURCE") "Digikey"))
      (libsource (lib "ScoreBoard") (part "QS/BCX70K00Z"))
    )
    (comp (ref "Q45")
      (value "BCX70K")
      (footprint "SOT23")
      (description "TRANS NPN AF 45V SOT-23")
      (fields (field (name "MANUFACTURER") "Fairchild Semiconductor") (field (name "SOURCE") "Digikey"))
      (libsource (lib "ScoreBoard") (part "QS/BCX70K00Z"))
    )
    (comp (ref "Q49")
      (value "BCX70K")
      (footprint "SOT23")
      (description "TRANS NPN AF 45V SOT-23")
      (fields (field (name "MANUFACTURER") "Fairchild Semiconductor") (field (name "SOURCE") "Digikey"))
      (libsource (lib "ScoreBoard") (part "QS/BCX70K00Z"))
    )
    (comp (ref "Q50")
      (value "BCX70K")
      (footprint "SOT23")
      (description "TRANS NPN AF 45V SOT-23")
      (fields (field (name "MANUFACTURER") "Fairchild Semiconductor") (field (name "SOURCE") "Digikey"))
      (libsource (lib "ScoreBoard") (part "QS/BCX70K00Z"))
    )
    (comp (ref "Q51")
      (value "BCX70K")
      (footprint "SOT23")
      (description "TRANS NPN AF 45V SOT-23")
      (fields (field (name "MANUFACTURER") "Fairchild Semiconductor") (field (name "SOURCE") "Digikey"))
      (libsource (lib "ScoreBoard") (part "QS/BCX70K00Z"))
    )
    (comp (ref "Q55")
      (value "BCX70K")
      (footprint "SOT23")
      (description "TRANS NPN AF 45V SOT-23")
      (fields (field (name "MANUFACTURER") "Fairchild Semiconductor") (field (name "SOURCE") "Digikey"))
      (libsource (lib "ScoreBoard") (part "QS/BCX70K00Z"))
    )
    (comp (ref "Q56")
      (value "BCX70K")
      (footprint "SOT23")
      (description "TRANS NPN AF 45V SOT-23")
      (fields (field (name "MANUFACTURER") "Fairchild Semiconductor") (field (name "SOURCE") "Digikey"))
      (libsource (lib "ScoreBoard") (part "QS/BCX70K00Z"))
    )
    (comp (ref "Q57")
      (value "BCX70K")
      (footprint "SOT23")
      (description "TRANS NPN AF 45V SOT-23")
      (fields (field (name "MANUFACTURER") "Fairchild Semiconductor") (field (name "SOURCE") "Digikey"))
      (libsource (lib "ScoreBoard") (part "QS/BCX70K00Z"))
    )
    (comp (ref "Q61")
      (value "BCX70K")
      (footprint "SOT23")
      (description "TRANS NPN AF 45V SOT-23")
      (fields (field (name "MANUFACTURER") "Fairchild Semiconductor") (field (name "SOURCE") "Digikey"))
      (libsource (lib "ScoreBoard") (part "QS/BCX70K00Z"))
    )
    (comp (ref "Q62")
      (value "BCX70K")
      (footprint "SOT23")
      (description "TRANS NPN AF 45V SOT-23")
      (fields (field (name "MANUFACTURER") "Fairchild Semiconductor") (field (name "SOURCE") "Digikey"))
      (libsource (lib "ScoreBoard") (part "QS/BCX70K00Z"))
    )
    (comp (ref "Q63")
      (value "BCX70K")
      (footprint "SOT23")
      (description "TRANS NPN AF 45V SOT-23")
      (fields (field (name "MANUFACTURER") "Fairchild Semiconductor") (field (name "SOURCE") "Digikey"))
      (libsource (lib "ScoreBoard") (part "QS/BCX70K00Z"))
    )
    (comp (ref "R108")
      (value "5.1k")
      (footprint "R0805")
      (description "RES 5.10K OHM 1/8W 1% 0805 SMD")
      (fields
        (field (name "MANUFACTURER") "Panasonic - ECG")
        (field (name "MANUFACTURER PART NUMBER") "ERJ-6ENF5101V")
      )
      (libsource (lib "eRCL") (part "ERJ-6ENF5101V"))
    )
    (comp (ref "R109")
      (value "5.1k")
      (footprint "R0805")
      (description "RES 5.10K OHM 1/8W 1% 0805 SMD")
      (fields
        (field (name "MANUFACTURER") "Panasonic - ECG")
        (field (name "MANUFACTURER PART NUMBER") "ERJ-6ENF5101V")
      )
      (libsource (lib "eRCL") (part "ERJ-6ENF5101V"))
    )
    (comp (ref "R110")
      (value "5.1k")
      (footprint "R0805")
      (description "RES 5.10K OHM 1/8W 1% 0805 SMD")
      (fields
        (field (name "MANUFACTURER") "Panasonic - ECG")
        (field (name "MANUFACTURER PART NUMBER") "ERJ-6ENF5101V")
      )
      (libsource (lib "eRCL") (part "ERJ-6ENF5101V"))
    )
    (comp (ref "R114")
      (value "120")
      (footprint "R1206")
      (description "RES 120 OHM 1/4W 1% 1206 SMD")
      (fields
        (field (name "MANUFACTURER") "Panasonic - ECG")
        (field (name "MANUFACTURER PART NUMBER") "ERJ-8ENF1200V")
      )
      (libsource (lib "eRCL") (part "ERJ-8ENF1200V"))
    )
    (comp (ref "R115")
      (value "120")
      (footprint "R1206")
      (description "RES 120 OHM 1/4W 1% 1206 SMD")
      (fields
        (field (name "MANUFACTURER") "Panasonic - ECG")
        (field (name "MANUFACTURER PART NUMBER") "ERJ-8ENF1200V")
      )
      (libsource (lib "eRCL") (part "ERJ-8ENF1200V"))
    )
    (comp (ref "R116")
      (value "120")
      (footprint "R1206")
      (description "RES 120 OHM 1/4W 1% 1206 SMD")
      (fields
        (field (name "MANUFACTURER") "Panasonic - ECG")
        (field (name "MANUFACTURER PART NUMBER") "ERJ-8ENF1200V")
      )
      (libsource (lib "eRCL") (part "ERJ-8ENF1200V"))
    )
    (comp (ref "R120")
      (value "120")
      (footprint "R1206")
      (description "RES 120 OHM 1/4W 1% 1206 SMD")
      (fields
        (field (name "MANUFACTURER") "Panasonic - ECG")
        (field (name "MANUFACTURER PART NUMBER") "ERJ-8ENF1200V")
      )
      (libsource (lib "eRCL") (part "ERJ-8ENF1200V"))
    )
    (comp (ref "R121")
      (value "120")
      (footprint "R1206")
      (description "RES 120 OHM 1/4W 1% 1206 SMD")
      (fields
        (field (name "MANUFACTURER") "Panasonic - ECG")
        (field (name "MANUFACTURER PART NUMBER") "ERJ-8ENF1200V")
      )
      (libsource (lib "eRCL") (part "ERJ-8ENF1200V"))
    )
    (comp (ref "R122")
      (value "120")
      (footprint "R1206")
      (description "RES 120 OHM 1/4W 1% 1206 SMD")
      (fields
        (field (name "MANUFACTURER") "Panasonic - ECG")
        (field (name "MANUFACTURER PART NUMBER") "ERJ-8ENF1200V")
      )
      (libsource (lib "eRCL") (part "ERJ-8ENF1200V"))
    )
    (comp (ref "R126")
      (value "5.1k")
      (footprint "R0805")
      (description "RES 5.10K OHM 1/8W 1% 0805 SMD")
      (fields
        (field (name "MANUFACTURER") "Panasonic - ECG")
        (field (name "MANUFACTURER PART NUMBER") "ERJ-6ENF5101V")
      )
      (libsource (lib "eRCL") (part "ERJ-6ENF5101V"))
    )
    (comp (ref "R127")
      (value "5.1k")
      (footprint "R0805")
      (description "RES 5.10K OHM 1/8W 1% 0805 SMD")
      (fields
        (field (name "MANUFACTURER") "Panasonic - ECG")
        (field (name "MANUFACTURER PART NUMBER") "ERJ-6ENF5101V")
      )
      (libsource (lib "eRCL") (part "ERJ-6ENF5101V"))
    )
    (comp (ref "R128")
      (value "5.1k")
      (footprint "R0805")
      (description "RES 5.10K OHM 1/8W 1% 0805 SMD")
      (fields
        (field (name "MANUFACTURER") "Panasonic - ECG")
        (field (name "MANUFACTURER PART NUMBER") "ERJ-6ENF5101V")
      )
      (libsource (lib "eRCL") (part "ERJ-6ENF5101V"))
    )
    (comp (ref "R132")
      (value "120")
      (footprint "R1206")
      (description "RES 120 OHM 1/4W 1% 1206 SMD")
      (fields
        (field (name "MANUFACTURER") "Panasonic - ECG")
        (field (name "MANUFACTURER PART NUMBER") "ERJ-8ENF1200V")
      )
      (libsource (lib "eRCL") (part "ERJ-8ENF1200V"))
    )
    (comp (ref "R133")
      (value "120")
      (footprint "R1206")
      (description "RES 120 OHM 1/4W 1% 1206 SMD")
      (fields
        (field (name "MANUFACTURER") "Panasonic - ECG")
        (field (name "MANUFACTURER PART NUMBER") "ERJ-8ENF1200V")
      )
      (libsource (lib "eRCL") (part "ERJ-8ENF1200V"))
    )
    (comp (ref "R134")
      (value "120")
      (footprint "R1206")
      (description "RES 120 OHM 1/4W 1% 1206 SMD")
      (fields
        (field (name "MANUFACTURER") "Panasonic - ECG")
        (field (name "MANUFACTURER PART NUMBER") "ERJ-8ENF1200V")
      )
      (libsource (lib "eRCL") (part "ERJ-8ENF1200V"))
    )
    (comp (ref "R138")
      (value "120")
      (footprint "R1206")
      (description "RES 120 OHM 1/4W 1% 1206 SMD")
      (fields
        (field (name "MANUFACTURER") "Panasonic - ECG")
        (field (name "MANUFACTURER PART NUMBER") "ERJ-8ENF1200V")
      )
      (libsource (lib "eRCL") (part "ERJ-8ENF1200V"))
    )
    (comp (ref "R139")
      (value "120")
      (footprint "R1206")
      (description "RES 120 OHM 1/4W 1% 1206 SMD")
      (fields
        (field (name "MANUFACTURER") "Panasonic - ECG")
        (field (name "MANUFACTURER PART NUMBER") "ERJ-8ENF1200V")
      )
      (libsource (lib "eRCL") (part "ERJ-8ENF1200V"))
    )
    (comp (ref "R140")
      (value "120")
      (footprint "R1206")
      (description "RES 120 OHM 1/4W 1% 1206 SMD")
      (fields
        (field (name "MANUFACTURER") "Panasonic - ECG")
        (field (name "MANUFACTURER PART NUMBER") "ERJ-8ENF1200V")
      )
      (libsource (lib "eRCL") (part "ERJ-8ENF1200V"))
    )
    (comp (ref "R144")
      (value "5.1k")
      (footprint "R0805")
      (description "RES 5.10K OHM 1/8W 1% 0805 SMD")
      (fields
        (field (name "MANUFACTURER") "Panasonic - ECG")
        (field (name "MANUFACTURER PART NUMBER") "ERJ-6ENF5101V")
      )
      (libsource (lib "eRCL") (part "ERJ-6ENF5101V"))
    )
    (comp (ref "R145")
      (value "5.1k")
      (footprint "R0805")
      (description "RES 5.10K OHM 1/8W 1% 0805 SMD")
      (fields
        (field (name "MANUFACTURER") "Panasonic - ECG")
        (field (name "MANUFACTURER PART NUMBER") "ERJ-6ENF5101V")
      )
      (libsource (lib "eRCL") (part "ERJ-6ENF5101V"))
    )
    (comp (ref "R146")
      (value "5.1k")
      (footprint "R0805")
      (description "RES 5.10K OHM 1/8W 1% 0805 SMD")
      (fields
        (field (name "MANUFACTURER") "Panasonic - ECG")
        (field (name "MANUFACTURER PART NUMBER") "ERJ-6ENF5101V")
      )
      (libsource (lib "eRCL") (part "ERJ-6ENF5101V"))
    )
    (comp (ref "R150")
      (value "120")
      (footprint "R1206")
      (description "RES 120 OHM 1/4W 1% 1206 SMD")
      (fields
        (field (name "MANUFACTURER") "Panasonic - ECG")
        (field (name "MANUFACTURER PART NUMBER") "ERJ-8ENF1200V")
      )
      (libsource (lib "eRCL") (part "ERJ-8ENF1200V"))
    )
    (comp (ref "R151")
      (value "120")
      (footprint "R1206")
      (description "RES 120 OHM 1/4W 1% 1206 SMD")
      (fields
        (field (name "MANUFACTURER") "Panasonic - ECG")
        (field (name "MANUFACTURER PART NUMBER") "ERJ-8ENF1200V")
      )
      (libsource (lib "eRCL") (part "ERJ-8ENF1200V"))
    )
    (comp (ref "R152")
      (value "120")
      (footprint "R1206")
      (description "RES 120 OHM 1/4W 1% 1206 SMD")
      (fields
        (field (name "MANUFACTURER") "Panasonic - ECG")
        (field (name "MANUFACTURER PART NUMBER") "ERJ-8ENF1200V")
      )
      (libsource (lib "eRCL") (part "ERJ-8ENF1200V"))
    )
    (comp (ref "R156")
      (value "120")
      (footprint "R1206")
      (description "RES 120 OHM 1/4W 1% 1206 SMD")
      (fields
        (field (name "MANUFACTURER") "Panasonic - ECG")
        (field (name "MANUFACTURER PART NUMBER") "ERJ-8ENF1200V")
      )
      (libsource (lib "eRCL") (part "ERJ-8ENF1200V"))
    )
    (comp (ref "R157")
      (value "120")
      (footprint "R1206")
      (description "RES 120 OHM 1/4W 1% 1206 SMD")
      (fields
        (field (name "MANUFACTURER") "Panasonic - ECG")
        (field (name "MANUFACTURER PART NUMBER") "ERJ-8ENF1200V")
      )
      (libsource (lib "eRCL") (part "ERJ-8ENF1200V"))
    )
    (comp (ref "R158")
      (value "120")
      (footprint "R1206")
      (description "RES 120 OHM 1/4W 1% 1206 SMD")
      (fields
        (field (name "MANUFACTURER") "Panasonic - ECG")
        (field (name "MANUFACTURER PART NUMBER") "ERJ-8ENF1200V")
      )
      (libsource (lib "eRCL") (part "ERJ-8ENF1200V"))
    )
    (comp (ref "R162")
      (value "5.1k")
      (footprint "R0805")
      (description "RES 5.10K OHM 1/8W 1% 0805 SMD")
      (fields
        (field (name "MANUFACTURER") "Panasonic - ECG")
        (field (name "MANUFACTURER PART NUMBER") "ERJ-6ENF5101V")
      )
      (libsource (lib "eRCL") (part "ERJ-6ENF5101V"))
    )
    (comp (ref "R163")
      (value "5.1k")
      (footprint "R0805")
      (description "RES 5.10K OHM 1/8W 1% 0805 SMD")
      (fields
        (field (name "MANUFACTURER") "Panasonic - ECG")
        (field (name "MANUFACTURER PART NUMBER") "ERJ-6ENF5101V")
      )
      (libsource (lib "eRCL") (part "ERJ-6ENF5101V"))
    )
    (comp (ref "R164")
      (value "5.1k")
      (footprint "R0805")
      (description "RES 5.10K OHM 1/8W 1% 0805 SMD")
      (fields
        (field (name "MANUFACTURER") "Panasonic - ECG")
        (field (name "MANUFACTURER PART NUMBER") "ERJ-6ENF5101V")
      )
      (libsource (lib "eRCL") (part "ERJ-6ENF5101V"))
    )
    (comp (ref "R168")
      (value "120")
      (footprint "R1206")
      (description "RES 120 OHM 1/4W 1% 1206 SMD")
      (fields
        (field (name "MANUFACTURER") "Panasonic - ECG")
        (field (name "MANUFACTURER PART NUMBER") "ERJ-8ENF1200V")
      )
      (libsource (lib "eRCL") (part "ERJ-8ENF1200V"))
    )
    (comp (ref "R169")
      (value "120")
      (footprint "R1206")
      (description "RES 120 OHM 1/4W 1% 1206 SMD")
      (fields
        (field (name "MANUFACTURER") "Panasonic - ECG")
        (field (name "MANUFACTURER PART NUMBER") "ERJ-8ENF1200V")
      )
      (libsource (lib "eRCL") (part "ERJ-8ENF1200V"))
    )
    (comp (ref "R170")
      (value "120")
      (footprint "R1206")
      (description "RES 120 OHM 1/4W 1% 1206 SMD")
      (fields
        (field (name "MANUFACTURER") "Panasonic - ECG")
        (field (name "MANUFACTURER PART NUMBER") "ERJ-8ENF1200V")
      )
      (libsource (lib "eRCL") (part "ERJ-8ENF1200V"))
    )
    (comp (ref "R174")
      (value "120")
      (footprint "R1206")
      (description "RES 120 OHM 1/4W 1% 1206 SMD")
      (fields
        (field (name "MANUFACTURER") "Panasonic - ECG")
        (field (name "MANUFACTURER PART NUMBER") "ERJ-8ENF1200V")
      )
      (libsource (lib "eRCL") (part "ERJ-8ENF1200V"))
    )
    (comp (ref "R175")
      (value "120")
      (footprint "R1206")
      (description "RES 120 OHM 1/4W 1% 1206 SMD")
      (fields
        (field (name "MANUFACTURER") "Panasonic - ECG")
        (field (name "MANUFACTURER PART NUMBER") "ERJ-8ENF1200V")
      )
      (libsource (lib "eRCL") (part "ERJ-8ENF1200V"))
    )
    (comp (ref "R176")
      (value "120")
      (footprint "R1206")
      (description "RES 120 OHM 1/4W 1% 1206 SMD")
      (fields
        (field (name "MANUFACTURER") "Panasonic - ECG")
        (field (name "MANUFACTURER PART NUMBER") "ERJ-8ENF1200V")
      )
      (libsource (lib "eRCL") (part "ERJ-8ENF1200V"))
    )
    (comp (ref "R180")
      (value "5.1k")
      (footprint "R0805")
      (description "RES 5.10K OHM 1/8W 1% 0805 SMD")
      (fields
        (field (name "MANUFACTURER") "Panasonic - ECG")
        (field (name "MANUFACTURER PART NUMBER") "ERJ-6ENF5101V")
      )
      (libsource (lib "eRCL") (part "ERJ-6ENF5101V"))
    )
    (comp (ref "R181")
      (value "5.1k")
      (footprint "R0805")
      (description "RES 5.10K OHM 1/8W 1% 0805 SMD")
      (fields
        (field (name "MANUFACTURER") "Panasonic - ECG")
        (field (name "MANUFACTURER PART NUMBER") "ERJ-6ENF5101V")
      )
      (libsource (lib "eRCL") (part "ERJ-6ENF5101V"))
    )
    (comp (ref "R182")
      (value "5.1k")
      (footprint "R0805")
      (description "RES 5.10K OHM 1/8W 1% 0805 SMD")
      (fields
        (field (name "MANUFACTURER") "Panasonic - ECG")
        (field (name "MANUFACTURER PART NUMBER") "ERJ-6ENF5101V")
      )
      (libsource (lib "eRCL") (part "ERJ-6ENF5101V"))
    )
    (comp (ref "R186")
      (value "120")
      (footprint "R1206")
      (description "RES 120 OHM 1/4W 1% 1206 SMD")
      (fields
        (field (name "MANUFACTURER") "Panasonic - ECG")
        (field (name "MANUFACTURER PART NUMBER") "ERJ-8ENF1200V")
      )
      (libsource (lib "eRCL") (part "ERJ-8ENF1200V"))
    )
    (comp (ref "R187")
      (value "120")
      (footprint "R1206")
      (description "RES 120 OHM 1/4W 1% 1206 SMD")
      (fields
        (field (name "MANUFACTURER") "Panasonic - ECG")
        (field (name "MANUFACTURER PART NUMBER") "ERJ-8ENF1200V")
      )
      (libsource (lib "eRCL") (part "ERJ-8ENF1200V"))
    )
    (comp (ref "R188")
      (value "120")
      (footprint "R1206")
      (description "RES 120 OHM 1/4W 1% 1206 SMD")
      (fields
        (field (name "MANUFACTURER") "Panasonic - ECG")
        (field (name "MANUFACTURER PART NUMBER") "ERJ-8ENF1200V")
      )
      (libsource (lib "eRCL") (part "ERJ-8ENF1200V"))
    )
    (comp (ref "R192")
      (value "120")
      (footprint "R1206")
      (description "RES 120 OHM 1/4W 1% 1206 SMD")
      (fields
        (field (name "MANUFACTURER") "Panasonic - ECG")
        (field (name "MANUFACTURER PART NUMBER") "ERJ-8ENF1200V")
      )
      (libsource (lib "eRCL") (part "ERJ-8ENF1200V"))
    )
    (comp (ref "R193")
      (value "120")
      (footprint "R1206")
      (description "RES 120 OHM 1/4W 1% 1206 SMD")
      (fields
        (field (name "MANUFACTURER") "Panasonic - ECG")
        (field (name "MANUFACTURER PART NUMBER") "ERJ-8ENF1200V")
      )
      (libsource (lib "eRCL") (part "ERJ-8ENF1200V"))
    )
    (comp (ref "R194")
      (value "120")
      (footprint "R1206")
      (description "RES 120 OHM 1/4W 1% 1206 SMD")
      (fields
        (field (name "MANUFACTURER") "Panasonic - ECG")
        (field (name "MANUFACTURER PART NUMBER") "ERJ-8ENF1200V")
      )
      (libsource (lib "eRCL") (part "ERJ-8ENF1200V"))
    )
    (comp (ref "R198")
      (value "5.1k")
      (footprint "R0805")
      (description "RES 5.10K OHM 1/8W 1% 0805 SMD")
      (fields
        (field (name "MANUFACTURER") "Panasonic - ECG")
        (field (name "MANUFACTURER PART NUMBER") "ERJ-6ENF5101V")
      )
      (libsource (lib "eRCL") (part "ERJ-6ENF5101V"))
    )
    (comp (ref "R199")
      (value "5.1k")
      (footprint "R0805")
      (description "RES 5.10K OHM 1/8W 1% 0805 SMD")
      (fields
        (field (name "MANUFACTURER") "Panasonic - ECG")
        (field (name "MANUFACTURER PART NUMBER") "ERJ-6ENF5101V")
      )
      (libsource (lib "eRCL") (part "ERJ-6ENF5101V"))
    )
    (comp (ref "R200")
      (value "5.1k")
      (footprint "R0805")
      (description "RES 5.10K OHM 1/8W 1% 0805 SMD")
      (fields
        (field (name "MANUFACTURER") "Panasonic - ECG")
        (field (name "MANUFACTURER PART NUMBER") "ERJ-6ENF5101V")
      )
      (libsource (lib "eRCL") (part "ERJ-6ENF5101V"))
    )
    (comp (ref "R204")
      (value "120")
      (footprint "R1206")
      (description "RES 120 OHM 1/4W 1% 1206 SMD")
      (fields
        (field (name "MANUFACTURER") "Panasonic - ECG")
        (field (name "MANUFACTURER PART NUMBER") "ERJ-8ENF1200V")
      )
      (libsource (lib "eRCL") (part "ERJ-8ENF1200V"))
    )
    (comp (ref "R205")
      (value "120")
      (footprint "R1206")
      (description "RES 120 OHM 1/4W 1% 1206 SMD")
      (fields
        (field (name "MANUFACTURER") "Panasonic - ECG")
        (field (name "MANUFACTURER PART NUMBER") "ERJ-8ENF1200V")
      )
      (libsource (lib "eRCL") (part "ERJ-8ENF1200V"))
    )
    (comp (ref "R206")
      (value "120")
      (footprint "R1206")
      (description "RES 120 OHM 1/4W 1% 1206 SMD")
      (fields
        (field (name "MANUFACTURER") "Panasonic - ECG")
        (field (name "MANUFACTURER PART NUMBER") "ERJ-8ENF1200V")
      )
      (libsource (lib "eRCL") (part "ERJ-8ENF1200V"))
    )
    (comp (ref "R210")
      (value "120")
      (footprint "R1206")
      (description "RES 120 OHM 1/4W 1% 1206 SMD")
      (fields
        (field (name "MANUFACTURER") "Panasonic - ECG")
        (field (name "MANUFACTURER PART NUMBER") "ERJ-8ENF1200V")
      )
      (libsource (lib "eRCL") (part "ERJ-8ENF1200V"))
    )
    (comp (ref "R211")
      (value "120")
      (footprint "R1206")
      (description "RES 120 OHM 1/4W 1% 1206 SMD")
      (fields
        (field (name "MANUFACTURER") "Panasonic - ECG")
        (field (name "MANUFACTURER PART NUMBER") "ERJ-8ENF1200V")
      )
      (libsource (lib "eRCL") (part "ERJ-8ENF1200V"))
    )
    (comp (ref "R212")
      (value "120")
      (footprint "R1206")
      (description "RES 120 OHM 1/4W 1% 1206 SMD")
      (fields
        (field (name "MANUFACTURER") "Panasonic - ECG")
        (field (name "MANUFACTURER PART NUMBER") "ERJ-8ENF1200V")
      )
      (libsource (lib "eRCL") (part "ERJ-8ENF1200V"))
    )
    (comp (ref "R216")
      (value "5.1k")
      (footprint "R0805")
      (description "RES 5.10K OHM 1/8W 1% 0805 SMD")
      (fields
        (field (name "MANUFACTURER") "Panasonic - ECG")
        (field (name "MANUFACTURER PART NUMBER") "ERJ-6ENF5101V")
      )
      (libsource (lib "eRCL") (part "ERJ-6ENF5101V"))
    )
    (comp (ref "R217")
      (value "5.1k")
      (footprint "R0805")
      (description "RES 5.10K OHM 1/8W 1% 0805 SMD")
      (fields
        (field (name "MANUFACTURER") "Panasonic - ECG")
        (field (name "MANUFACTURER PART NUMBER") "ERJ-6ENF5101V")
      )
      (libsource (lib "eRCL") (part "ERJ-6ENF5101V"))
    )
    (comp (ref "R218")
      (value "5.1k")
      (footprint "R0805")
      (description "RES 5.10K OHM 1/8W 1% 0805 SMD")
      (fields
        (field (name "MANUFACTURER") "Panasonic - ECG")
        (field (name "MANUFACTURER PART NUMBER") "ERJ-6ENF5101V")
      )
      (libsource (lib "eRCL") (part "ERJ-6ENF5101V"))
    )
    (comp (ref "R222")
      (value "120")
      (footprint "R1206")
      (description "RES 120 OHM 1/4W 1% 1206 SMD")
      (fields
        (field (name "MANUFACTURER") "Panasonic - ECG")
        (field (name "MANUFACTURER PART NUMBER") "ERJ-8ENF1200V")
      )
      (libsource (lib "eRCL") (part "ERJ-8ENF1200V"))
    )
    (comp (ref "R223")
      (value "120")
      (footprint "R1206")
      (description "RES 120 OHM 1/4W 1% 1206 SMD")
      (fields
        (field (name "MANUFACTURER") "Panasonic - ECG")
        (field (name "MANUFACTURER PART NUMBER") "ERJ-8ENF1200V")
      )
      (libsource (lib "eRCL") (part "ERJ-8ENF1200V"))
    )
    (comp (ref "R224")
      (value "120")
      (footprint "R1206")
      (description "RES 120 OHM 1/4W 1% 1206 SMD")
      (fields
        (field (name "MANUFACTURER") "Panasonic - ECG")
        (field (name "MANUFACTURER PART NUMBER") "ERJ-8ENF1200V")
      )
      (libsource (lib "eRCL") (part "ERJ-8ENF1200V"))
    )
    (comp (ref "R228")
      (value "120")
      (footprint "R1206")
      (description "RES 120 OHM 1/4W 1% 1206 SMD")
      (fields
        (field (name "MANUFACTURER") "Panasonic - ECG")
        (field (name "MANUFACTURER PART NUMBER") "ERJ-8ENF1200V")
      )
      (libsource (lib "eRCL") (part "ERJ-8ENF1200V"))
    )
    (comp (ref "R229")
      (value "120")
      (footprint "R1206")
      (description "RES 120 OHM 1/4W 1% 1206 SMD")
      (fields
        (field (name "MANUFACTURER") "Panasonic - ECG")
        (field (name "MANUFACTURER PART NUMBER") "ERJ-8ENF1200V")
      )
      (libsource (lib "eRCL") (part "ERJ-8ENF1200V"))
    )
    (comp (ref "R230")
      (value "120")
      (footprint "R1206")
      (description "RES 120 OHM 1/4W 1% 1206 SMD")
      (fields
        (field (name "MANUFACTURER") "Panasonic - ECG")
        (field (name "MANUFACTURER PART NUMBER") "ERJ-8ENF1200V")
      )
      (libsource (lib "eRCL") (part "ERJ-8ENF1200V"))
    )
    (comp (ref "U22")
      (value "IS/SN74HC573DWZ")
      (footprint "SOIC300-20")
      (description "Octal D-Type Transparent Latch with 3-State Outputs")
      (fields
        (field (name "MANUFACTURER") "NXP Semiconductors")
        (field (name "MANUFACTURER PART NUMBER") "74HC573D-T")
        (field (name "SOURCE") "Digikey")
      )
      (libsource (lib "ScoreBoard") (part "IS/SN74HC573DWZ"))
    )
    (comp (ref "U23")
      (value "IS/SN74HC573DWZ")
      (footprint "SOIC300-20")
      (description "Octal D-Type Transparent Latch with 3-State Outputs")
      (fields
        (field (name "MANUFACTURER") "NXP Semiconductors")
        (field (name "MANUFACTURER PART NUMBER") "74HC573D-T")
        (field (name "SOURCE") "Digikey")
      )
      (libsource (lib "ScoreBoard") (part "IS/SN74HC573DWZ"))
    )
    (comp (ref "U24")
      (value "IS/SN74HC573DWZ")
      (footprint "SOIC300-20")
      (description "Octal D-Type Transparent Latch with 3-State Outputs")
      (fields
        (field (name "MANUFACTURER") "NXP Semiconductors")
        (field (name "MANUFACTURER PART NUMBER") "74HC573D-T")
        (field (name "SOURCE") "Digikey")
      )
      (libsource (lib "ScoreBoard") (part "IS/SN74HC573DWZ"))
    )
  )
  (nets
    (net (code "1") (name "/8V") (class "Default")
      (node (ref "DS103") (pin "1") (pinfunction "A_1") (pintype "passive"))
      (node (ref "DS105") (pin "1") (pinfunction "A_1") (pintype "passive"))
      (node (ref "DS107") (pin "1") (pinfunction "A_1") (pintype "passive"))
      (node (ref "DS11") (pin "1") (pinfunction "A_1") (pintype "passive"))
      (node (ref "DS115") (pin "1") (pinfunction "A_1") (pintype "passive"))
      (node (ref "DS117") (pin "1") (pinfunction "A_1") (pintype "passive"))
      (node (ref "DS119") (pin "1") (pinfunction "A_1") (pintype "passive"))
      (node (ref "DS127") (pin "1") (pinfunction "A_1") (pintype "passive"))
      (node (ref "DS129") (pin "1") (pinfunction "A_1") (pintype "passive"))
      (node (ref "DS131") (pin "1") (pinfunction "A_1") (pintype "passive"))
      (node (ref "DS139") (pin "1") (pinfunction "A_1") (pintype "passive"))
      (node (ref "DS141") (pin "1") (pinfunction "A_1") (pintype "passive"))
      (node (ref "DS143") (pin "1") (pinfunction "A_1") (pintype "passive"))
      (node (ref "DS151") (pin "1") (pinfunction "A_1") (pintype "passive"))
      (node (ref "DS153") (pin "1") (pinfunction "A_1") (pintype "passive"))
      (node (ref "DS155") (pin "1") (pinfunction "A_1") (pintype "passive"))
      (node (ref "DS163") (pin "1") (pinfunction "A_1") (pintype "passive"))
      (node (ref "DS165") (pin "1") (pinfunction "A_1") (pintype "passive"))
      (node (ref "DS167") (pin "1") (pinfunction "A_1") (pintype "passive"))
      (node (ref "DS19") (pin "1") (pinfunction "A_1") (pintype "passive"))
      (node (ref "DS21") (pin "1") (pinfunction "A_1") (pintype "passive"))
      (node (ref "DS23") (pin "1") (pinfunction "A_1") (pintype "passive"))
      (node (ref "DS31") (pin "1") (pinfunction "A_1") (pintype "passive"))
      (node (ref "DS33") (pin "1") (pinfunction "A_1") (pintype "passive"))
      (node (ref "DS35") (pin "1") (pinfunction "A_1") (pintype "passive"))
      (node (ref "DS43") (pin "1") (pinfunction "A_1") (pintype "passive"))
      (node (ref "DS45") (pin "1") (pinfunction "A_1") (pintype "passive"))
      (node (ref "DS47") (pin "1") (pinfunction "A_1") (pintype "passive"))
      (node (ref "DS55") (pin "1") (pinfunction "A_1") (pintype "passive"))
      (node (ref "DS57") (pin "1") (pinfunction "A_1") (pintype "passive"))
      (node (ref "DS59") (pin "1") (pinfunction "A_1") (pintype "passive"))
      (node (ref "DS67") (pin "1") (pinfunction "A_1") (pintype "passive"))
      (node (ref "DS69") (pin "1") (pinfunction "A_1") (pintype "passive"))
      (node (ref "DS7") (pin "1") (pinfunction "A_1") (pintype "passive"))
      (node (ref "DS71") (pin "1") (pinfunction "A_1") (pintype "passive"))
      (node (ref "DS79") (pin "1") (pinfunction "A_1") (pintype "passive"))
      (node (ref "DS81") (pin "1") (pinfunction "A_1") (pintype "passive"))
      (node (ref "DS83") (pin "1") (pinfunction "A_1") (pintype "passive"))
      (node (ref "DS9") (pin "1") (pinfunction "A_1") (pintype "passive"))
      (node (ref "DS91") (pin "1") (pinfunction "A_1") (pintype "passive"))
      (node (ref "DS93") (pin "1") (pinfunction "A_1") (pintype "passive"))
      (node (ref "DS95") (pin "1") (pinfunction "A_1") (pintype "passive"))
    )
    (net (code "2") (name "/CLK3") (class "Default")
      (node (ref "U22") (pin "11") (pinfunction "LE_11") (pintype "input"))
    )
    (net (code "3") (name "/CLK4") (class "Default")
      (node (ref "U23") (pin "11") (pinfunction "LE_11") (pintype "input"))
    )
    (net (code "4") (name "/CLK5") (class "Default")
      (node (ref "U24") (pin "11") (pinfunction "LE_11") (pintype "input"))
    )
    (net (code "5") (name "/D0") (class "Default")
      (node (ref "U22") (pin "2") (pinfunction "D1_2") (pintype "input"))
      (node (ref "U23") (pin "2") (pinfunction "D1_2") (pintype "input"))
      (node (ref "U24") (pin "2") (pinfunction "D1_2") (pintype "input"))
    )
    (net (code "6") (name "/D1") (class "Default")
      (node (ref "U22") (pin "3") (pinfunction "D2_3") (pintype "input"))
      (node (ref "U23") (pin "3") (pinfunction "D2_3") (pintype "input"))
      (node (ref "U24") (pin "3") (pinfunction "D2_3") (pintype "input"))
    )
    (net (code "7") (name "/D2") (class "Default")
      (node (ref "U22") (pin "4") (pinfunction "D3_4") (pintype "input"))
      (node (ref "U23") (pin "4") (pinfunction "D3_4") (pintype "input"))
      (node (ref "U24") (pin "4") (pinfunction "D3_4") (pintype "input"))
    )
    (net (code "8") (name "/D3") (class "Default")
      (node (ref "U22") (pin "5") (pinfunction "D4_5") (pintype "input"))
      (node (ref "U23") (pin "5") (pinfunction "D4_5") (pintype "input"))
      (node (ref "U24") (pin "5") (pinfunction "D4_5") (pintype "input"))
    )
    (net (code "9") (name "/D4") (class "Default")
      (node (ref "U22") (pin "6") (pinfunction "D5_6") (pintype "input"))
      (node (ref "U23") (pin "6") (pinfunction "D5_6") (pintype "input"))
      (node (ref "U24") (pin "6") (pinfunction "D5_6") (pintype "input"))
    )
    (net (code "10") (name "/D5") (class "Default")
      (node (ref "U22") (pin "7") (pinfunction "D6_7") (pintype "input"))
      (node (ref "U23") (pin "7") (pinfunction "D6_7") (pintype "input"))
      (node (ref "U24") (pin "7") (pinfunction "D6_7") (pintype "input"))
    )
    (net (code "11") (name "/D6") (class "Default")
      (node (ref "U22") (pin "8") (pinfunction "D7_8") (pintype "input"))
      (node (ref "U23") (pin "8") (pinfunction "D7_8") (pintype "input"))
      (node (ref "U24") (pin "8") (pinfunction "D7_8") (pintype "input"))
    )
    (net (code "12") (name "/D7") (class "Default")
      (node (ref "U22") (pin "9") (pinfunction "D8_9") (pintype "input"))
      (node (ref "U23") (pin "9") (pinfunction "D8_9") (pintype "input"))
      (node (ref "U24") (pin "9") (pinfunction "D8_9") (pintype "input"))
    )
    (net (code "13") (name "/LAMP3") (class "Default")
      (node (ref "U22") (pin "12") (pinfunction "Q8_12") (pintype "tri_state"))
    )
    (net (code "14") (name "/LAMP4") (class "Default")
      (node (ref "U23") (pin "12") (pinfunction "Q8_12") (pintype "tri_state"))
    )
    (net (code "15") (name "/LAMP5") (class "Default")
      (node (ref "U24") (pin "12") (pinfunction "Q8_12") (pintype "tri_state"))
    )
    (net (code "16") (name "/LED_OE") (class "Default")
      (node (ref "U22") (pin "1") (pinfunction "~{OE}_1") (pintype "input"))
      (node (ref "U23") (pin "1") (pinfunction "~{OE}_1") (pintype "input"))
      (node (ref "U24") (pin "1") (pinfunction "~{OE}_1") (pintype "input"))
    )
    (net (code "17") (name "GND") (class "Default")
      (node (ref "C50") (pin "2") (pinfunction "2_2") (pintype "passive"))
      (node (ref "C51") (pin "2") (pinfunction "2_2") (pintype "passive"))
      (node (ref "C52") (pin "2") (pinfunction "2_2") (pintype "passive"))
      (node (ref "Q25") (pin "2") (pinfunction "E_2") (pintype "passive"))
      (node (ref "Q26") (pin "2") (pinfunction "E_2") (pintype "passive"))
      (node (ref "Q27") (pin "2") (pinfunction "E_2") (pintype "passive"))
      (node (ref "Q31") (pin "2") (pinfunction "E_2") (pintype "passive"))
      (node (ref "Q32") (pin "2") (pinfunction "E_2") (pintype "passive"))
      (node (ref "Q33") (pin "2") (pinfunction "E_2") (pintype "passive"))
      (node (ref "Q37") (pin "2") (pinfunction "E_2") (pintype "passive"))
      (node (ref "Q38") (pin "2") (pinfunction "E_2") (pintype "passive"))
      (node (ref "Q39") (pin "2") (pinfunction "E_2") (pintype "passive"))
      (node (ref "Q43") (pin "2") (pinfunction "E_2") (pintype "passive"))
      (node (ref "Q44") (pin "2") (pinfunction "E_2") (pintype "passive"))
      (node (ref "Q45") (pin "2") (pinfunction "E_2") (pintype "passive"))
      (node (ref "Q49") (pin "2") (pinfunction "E_2") (pintype "passive"))
      (node (ref "Q50") (pin "2") (pinfunction "E_2") (pintype "passive"))
      (node (ref "Q51") (pin "2") (pinfunction "E_2") (pintype "passive"))
      (node (ref "Q55") (pin "2") (pinfunction "E_2") (pintype "passive"))
      (node (ref "Q56") (pin "2") (pinfunction "E_2") (pintype "passive"))
      (node (ref "Q57") (pin "2") (pinfunction "E_2") (pintype "passive"))
      (node (ref "Q61") (pin "2") (pinfunction "E_2") (pintype "passive"))
      (node (ref "Q62") (pin "2") (pinfunction "E_2") (pintype "passive"))
      (node (ref "Q63") (pin "2") (pinfunction "E_2") (pintype "passive"))
      (node (ref "U22") (pin "10") (pinfunction "GND_10") (pintype "power_in"))
      (node (ref "U23") (pin "10") (pinfunction "GND_10") (pintype "power_in"))
      (node (ref "U24") (pin "10") (pinfunction "GND_10") (pintype "power_in"))
    )
    (net (code "18") (name "Net-(DS7-K)") (class "Default")
      (node (ref "DS7") (pin "2") (pinfunction "K_2") (pintype "passive"))
      (node (ref "DS8") (pin "1") (pinfunction "A_1") (pintype "passive"))
    )
    (net (code "19") (name "Net-(DS8-K)") (class "Default")
      (node (ref "DS8") (pin "2") (pinfunction "K_2") (pintype "passive"))
      (node (ref "R114") (pin "2") (pinfunction "2_2") (pintype "passive"))
    )
    (net (code "20") (name "Net-(DS10-A)") (class "Default")
      (node (ref "DS10") (pin "1") (pinfunction "A_1") (pintype "passive"))
      (node (ref "DS9") (pin "2") (pinfunction "K_2") (pintype "passive"))
    )
    (net (code "21") (name "Net-(DS10-K)") (class "Default")
      (node (ref "DS10") (pin "2") (pinfunction "K_2") (pintype "passive"))
      (node (ref "R115") (pin "2") (pinfunction "2_2") (pintype "passive"))
    )
    (net (code "22") (name "Net-(DS11-K)") (class "Default")
      (node (ref "DS11") (pin "2") (pinfunction "K_2") (pintype "passive"))
      (node (ref "DS12") (pin "1") (pinfunction "A_1") (pintype "passive"))
    )
    (net (code "23") (name "Net-(DS12-K)") (class "Default")
      (node (ref "DS12") (pin "2") (pinfunction "K_2") (pintype "passive"))
      (node (ref "R116") (pin "2") (pinfunction "2_2") (pintype "passive"))
    )
    (net (code "24") (name "Net-(DS19-K)") (class "Default")
      (node (ref "DS19") (pin "2") (pinfunction "K_2") (pintype "passive"))
      (node (ref "DS20") (pin "1") (pinfunction "A_1") (pintype "passive"))
    )
    (net (code "25") (name "Net-(DS20-K)") (class "Default")
      (node (ref "DS20") (pin "2") (pinfunction "K_2") (pintype "passive"))
      (node (ref "R120") (pin "2") (pinfunction "2_2") (pintype "passive"))
    )
    (net (code "26") (name "Net-(DS21-K)") (class "Default")
      (node (ref "DS21") (pin "2") (pinfunction "K_2") (pintype "passive"))
      (node (ref "DS22") (pin "1") (pinfunction "A_1") (pintype "passive"))
    )
    (net (code "27") (name "Net-(DS22-K)") (class "Default")
      (node (ref "DS22") (pin "2") (pinfunction "K_2") (pintype "passive"))
      (node (ref "R121") (pin "2") (pinfunction "2_2") (pintype "passive"))
    )
    (net (code "28") (name "Net-(DS23-K)") (class "Default")
      (node (ref "DS23") (pin "2") (pinfunction "K_2") (pintype "passive"))
      (node (ref "DS24") (pin "1") (pinfunction "A_1") (pintype "passive"))
    )
    (net (code "29") (name "Net-(DS24-K)") (class "Default")
      (node (ref "DS24") (pin "2") (pinfunction "K_2") (pintype "passive"))
      (node (ref "R122") (pin "2") (pinfunction "2_2") (pintype "passive"))
    )
    (net (code "30") (name "Net-(DS31-K)") (class "Default")
      (node (ref "DS31") (pin "2") (pinfunction "K_2") (pintype "passive"))
      (node (ref "DS32") (pin "1") (pinfunction "A_1") (pintype "passive"))
    )
    (net (code "31") (name "Net-(DS32-K)") (class "Default")
      (node (ref "DS32") (pin "2") (pinfunction "K_2") (pintype "passive"))
      (node (ref "R132") (pin "2") (pinfunction "2_2") (pintype "passive"))
    )
    (net (code "32") (name "Net-(DS33-K)") (class "Default")
      (node (ref "DS33") (pin "2") (pinfunction "K_2") (pintype "passive"))
      (node (ref "DS34") (pin "1") (pinfunction "A_1") (pintype "passive"))
    )
    (net (code "33") (name "Net-(DS34-K)") (class "Default")
      (node (ref "DS34") (pin "2") (pinfunction "K_2") (pintype "passive"))
      (node (ref "R133") (pin "2") (pinfunction "2_2") (pintype "passive"))
    )
    (net (code "34") (name "Net-(DS35-K)") (class "Default")
      (node (ref "DS35") (pin "2") (pinfunction "K_2") (pintype "passive"))
      (node (ref "DS36") (pin "1") (pinfunction "A_1") (pintype "passive"))
    )
    (net (code "35") (name "Net-(DS36-K)") (class "Default")
      (node (ref "DS36") (pin "2") (pinfunction "K_2") (pintype "passive"))
      (node (ref "R134") (pin "2") (pinfunction "2_2") (pintype "passive"))
    )
    (net (code "36") (name "Net-(DS43-K)") (class "Default")
      (node (ref "DS43") (pin "2") (pinfunction "K_2") (pintype "passive"))
      (node (ref "DS44") (pin "1") (pinfunction "A_1") (pintype "passive"))
    )
    (net (code "37") (name "Net-(DS44-K)") (class "Default")
      (node (ref "DS44") (pin "2") (pinfunction "K_2") (pintype "passive"))
      (node (ref "R138") (pin "2") (pinfunction "2_2") (pintype "passive"))
    )
    (net (code "38") (name "Net-(DS45-K)") (class "Default")
      (node (ref "DS45") (pin "2") (pinfunction "K_2") (pintype "passive"))
      (node (ref "DS46") (pin "1") (pinfunction "A_1") (pintype "passive"))
    )
    (net (code "39") (name "Net-(DS46-K)") (class "Default")
      (node (ref "DS46") (pin "2") (pinfunction "K_2") (pintype "passive"))
      (node (ref "R139") (pin "2") (pinfunction "2_2") (pintype "passive"))
    )
    (net (code "40") (name "Net-(DS47-K)") (class "Default")
      (node (ref "DS47") (pin "2") (pinfunction "K_2") (pintype "passive"))
      (node (ref "DS48") (pin "1") (pinfunction "A_1") (pintype "passive"))
    )
    (net (code "41") (name "Net-(DS48-K)") (class "Default")
      (node (ref "DS48") (pin "2") (pinfunction "K_2") (pintype "passive"))
      (node (ref "R140") (pin "2") (pinfunction "2_2") (pintype "passive"))
    )
    (net (code "42") (name "Net-(DS55-K)") (class "Default")
      (node (ref "DS55") (pin "2") (pinfunction "K_2") (pintype "passive"))
      (node (ref "DS56") (pin "1") (pinfunction "A_1") (pintype "passive"))
    )
    (net (code "43") (name "Net-(DS56-K)") (class "Default")
      (node (ref "DS56") (pin "2") (pinfunction "K_2") (pintype "passive"))
      (node (ref "R150") (pin "2") (pinfunction "2_2") (pintype "passive"))
    )
    (net (code "44") (name "Net-(DS57-K)") (class "Default")
      (node (ref "DS57") (pin "2") (pinfunction "K_2") (pintype "passive"))
      (node (ref "DS58") (pin "1") (pinfunction "A_1") (pintype "passive"))
    )
    (net (code "45") (name "Net-(DS58-K)") (class "Default")
      (node (ref "DS58") (pin "2") (pinfunction "K_2") (pintype "passive"))
      (node (ref "R151") (pin "2") (pinfunction "2_2") (pintype "passive"))
    )
    (net (code "46") (name "Net-(DS59-K)") (class "Default")
      (node (ref "DS59") (pin "2") (pinfunction "K_2") (pintype "passive"))
      (node (ref "DS60") (pin "1") (pinfunction "A_1") (pintype "passive"))
    )
    (net (code "47") (name "Net-(DS60-K)") (class "Default")
      (node (ref "DS60") (pin "2") (pinfunction "K_2") (pintype "passive"))
      (node (ref "R152") (pin "2") (pinfunction "2_2") (pintype "passive"))
    )
    (net (code "48") (name "Net-(DS67-K)") (class "Default")
      (node (ref "DS67") (pin "2") (pinfunction "K_2") (pintype "passive"))
      (node (ref "DS68") (pin "1") (pinfunction "A_1") (pintype "passive"))
    )
    (net (code "49") (name "Net-(DS68-K)") (class "Default")
      (node (ref "DS68") (pin "2") (pinfunction "K_2") (pintype "passive"))
      (node (ref "R156") (pin "2") (pinfunction "2_2") (pintype "passive"))
    )
    (net (code "50") (name "Net-(DS69-K)") (class "Default")
      (node (ref "DS69") (pin "2") (pinfunction "K_2") (pintype "passive"))
      (node (ref "DS70") (pin "1") (pinfunction "A_1") (pintype "passive"))
    )
    (net (code "51") (name "Net-(DS70-K)") (class "Default")
      (node (ref "DS70") (pin "2") (pinfunction "K_2") (pintype "passive"))
      (node (ref "R157") (pin "2") (pinfunction "2_2") (pintype "passive"))
    )
    (net (code "52") (name "Net-(DS71-K)") (class "Default")
      (node (ref "DS71") (pin "2") (pinfunction "K_2") (pintype "passive"))
      (node (ref "DS72") (pin "1") (pinfunction "A_1") (pintype "passive"))
    )
    (net (code "53") (name "Net-(DS72-K)") (class "Default")
      (node (ref "DS72") (pin "2") (pinfunction "K_2") (pintype "passive"))
      (node (ref "R158") (pin "2") (pinfunction "2_2") (pintype "passive"))
    )
    (net (code "54") (name "Net-(DS79-K)") (class "Default")
      (node (ref "DS79") (pin "2") (pinfunction "K_2") (pintype "passive"))
      (node (ref "DS80") (pin "1") (pinfunction "A_1") (pintype "passive"))
    )
    (net (code "55") (name "Net-(DS80-K)") (class "Default")
      (node (ref "DS80") (pin "2") (pinfunction "K_2") (pintype "passive"))
      (node (ref "R168") (pin "2") (pinfunction "2_2") (pintype "passive"))
    )
    (net (code "56") (name "Net-(DS81-K)") (class "Default")
      (node (ref "DS81") (pin "2") (pinfunction "K_2") (pintype "passive"))
      (node (ref "DS82") (pin "1") (pinfunction "A_1") (pintype "passive"))
    )
    (net (code "57") (name "Net-(DS82-K)") (class "Default")
      (node (ref "DS82") (pin "2") (pinfunction "K_2") (pintype "passive"))
      (node (ref "R169") (pin "2") (pinfunction "2_2") (pintype "passive"))
    )
    (net (code "58") (name "Net-(DS83-K)") (class "Default")
      (node (ref "DS83") (pin "2") (pinfunction "K_2") (pintype "passive"))
      (node (ref "DS84") (pin "1") (pinfunction "A_1") (pintype "passive"))
    )
    (net (code "59") (name "Net-(DS84-K)") (class "Default")
      (node (ref "DS84") (pin "2") (pinfunction "K_2") (pintype "passive"))
      (node (ref "R170") (pin "2") (pinfunction "2_2") (pintype "passive"))
    )
    (net (code "60") (name "Net-(DS91-K)") (class "Default")
      (node (ref "DS91") (pin "2") (pinfunction "K_2") (pintype "passive"))
      (node (ref "DS92") (pin "1") (pinfunction "A_1") (pintype "passive"))
    )
    (net (code "61") (name "Net-(DS92-K)") (class "Default")
      (node (ref "DS92") (pin "2") (pinfunction "K_2") (pintype "passive"))
      (node (ref "R174") (pin "2") (pinfunction "2_2") (pintype "passive"))
    )
    (net (code "62") (name "Net-(DS93-K)") (class "Default")
      (node (ref "DS93") (pin "2") (pinfunction "K_2") (pintype "passive"))
      (node (ref "DS94") (pin "1") (pinfunction "A_1") (pintype "passive"))
    )
    (net (code "63") (name "Net-(DS94-K)") (class "Default")
      (node (ref "DS94") (pin "2") (pinfunction "K_2") (pintype "passive"))
      (node (ref "R175") (pin "2") (pinfunction "2_2") (pintype "passive"))
    )
    (net (code "64") (name "Net-(DS95-K)") (class "Default")
      (node (ref "DS95") (pin "2") (pinfunction "K_2") (pintype "passive"))
      (node (ref "DS96") (pin "1") (pinfunction "A_1") (pintype "passive"))
    )
    (net (code "65") (name "Net-(DS96-K)") (class "Default")
      (node (ref "DS96") (pin "2") (pinfunction "K_2") (pintype "passive"))
      (node (ref "R176") (pin "2") (pinfunction "2_2") (pintype "passive"))
    )
    (net (code "66") (name "Net-(DS103-K)") (class "Default")
      (node (ref "DS103") (pin "2") (pinfunction "K_2") (pintype "passive"))
      (node (ref "DS104") (pin "1") (pinfunction "A_1") (pintype "passive"))
    )
    (net (code "67") (name "Net-(DS104-K)") (class "Default")
      (node (ref "DS104") (pin "2") (pinfunction "K_2") (pintype "passive"))
      (node (ref "R186") (pin "2") (pinfunction "2_2") (pintype "passive"))
    )
    (net (code "68") (name "Net-(DS105-K)") (class "Default")
      (node (ref "DS105") (pin "2") (pinfunction "K_2") (pintype "passive"))
      (node (ref "DS106") (pin "1") (pinfunction "A_1") (pintype "passive"))
    )
    (net (code "69") (name "Net-(DS106-K)") (class "Default")
      (node (ref "DS106") (pin "2") (pinfunction "K_2") (pintype "passive"))
      (node (ref "R187") (pin "2") (pinfunction "2_2") (pintype "passive"))
    )
    (net (code "70") (name "Net-(DS107-K)") (class "Default")
      (node (ref "DS107") (pin "2") (pinfunction "K_2") (pintype "passive"))
      (node (ref "DS108") (pin "1") (pinfunction "A_1") (pintype "passive"))
    )
    (net (code "71") (name "Net-(DS108-K)") (class "Default")
      (node (ref "DS108") (pin "2") (pinfunction "K_2") (pintype "passive"))
      (node (ref "R188") (pin "2") (pinfunction "2_2") (pintype "passive"))
    )
    (net (code "72") (name "Net-(DS115-K)") (class "Default")
      (node (ref "DS115") (pin "2") (pinfunction "K_2") (pintype "passive"))
      (node (ref "DS116") (pin "1") (pinfunction "A_1") (pintype "passive"))
    )
    (net (code "73") (name "Net-(DS116-K)") (class "Default")
      (node (ref "DS116") (pin "2") (pinfunction "K_2") (pintype "passive"))
      (node (ref "R192") (pin "2") (pinfunction "2_2") (pintype "passive"))
    )
    (net (code "74") (name "Net-(DS117-K)") (class "Default")
      (node (ref "DS117") (pin "2") (pinfunction "K_2") (pintype "passive"))
      (node (ref "DS118") (pin "1") (pinfunction "A_1") (pintype "passive"))
    )
    (net (code "75") (name "Net-(DS118-K)") (class "Default")
      (node (ref "DS118") (pin "2") (pinfunction "K_2") (pintype "passive"))
      (node (ref "R193") (pin "2") (pinfunction "2_2") (pintype "passive"))
    )
    (net (code "76") (name "Net-(DS119-K)") (class "Default")
      (node (ref "DS119") (pin "2") (pinfunction "K_2") (pintype "passive"))
      (node (ref "DS120") (pin "1") (pinfunction "A_1") (pintype "passive"))
    )
    (net (code "77") (name "Net-(DS120-K)") (class "Default")
      (node (ref "DS120") (pin "2") (pinfunction "K_2") (pintype "passive"))
      (node (ref "R194") (pin "2") (pinfunction "2_2") (pintype "passive"))
    )
    (net (code "78") (name "Net-(DS127-K)") (class "Default")
      (node (ref "DS127") (pin "2") (pinfunction "K_2") (pintype "passive"))
      (node (ref "DS128") (pin "1") (pinfunction "A_1") (pintype "passive"))
    )
    (net (code "79") (name "Net-(DS128-K)") (class "Default")
      (node (ref "DS128") (pin "2") (pinfunction "K_2") (pintype "passive"))
      (node (ref "R204") (pin "2") (pinfunction "2_2") (pintype "passive"))
    )
    (net (code "80") (name "Net-(DS129-K)") (class "Default")
      (node (ref "DS129") (pin "2") (pinfunction "K_2") (pintype "passive"))
      (node (ref "DS130") (pin "1") (pinfunction "A_1") (pintype "passive"))
    )
    (net (code "81") (name "Net-(DS130-K)") (class "Default")
      (node (ref "DS130") (pin "2") (pinfunction "K_2") (pintype "passive"))
      (node (ref "R205") (pin "2") (pinfunction "2_2") (pintype "passive"))
    )
    (net (code "82") (name "Net-(DS131-K)") (class "Default")
      (node (ref "DS131") (pin "2") (pinfunction "K_2") (pintype "passive"))
      (node (ref "DS132") (pin "1") (pinfunction "A_1") (pintype "passive"))
    )
    (net (code "83") (name "Net-(DS132-K)") (class "Default")
      (node (ref "DS132") (pin "2") (pinfunction "K_2") (pintype "passive"))
      (node (ref "R206") (pin "2") (pinfunction "2_2") (pintype "passive"))
    )
    (net (code "84") (name "Net-(DS139-K)") (class "Default")
      (node (ref "DS139") (pin "2") (pinfunction "K_2") (pintype "passive"))
      (node (ref "DS140") (pin "1") (pinfunction "A_1") (pintype "passive"))
    )
    (net (code "85") (name "Net-(DS140-K)") (class "Default")
      (node (ref "DS140") (pin "2") (pinfunction "K_2") (pintype "passive"))
      (node (ref "R210") (pin "2") (pinfunction "2_2") (pintype "passive"))
    )
    (net (code "86") (name "Net-(DS141-K)") (class "Default")
      (node (ref "DS141") (pin "2") (pinfunction "K_2") (pintype "passive"))
      (node (ref "DS142") (pin "1") (pinfunction "A_1") (pintype "passive"))
    )
    (net (code "87") (name "Net-(DS142-K)") (class "Default")
      (node (ref "DS142") (pin "2") (pinfunction "K_2") (pintype "passive"))
      (node (ref "R211") (pin "2") (pinfunction "2_2") (pintype "passive"))
    )
    (net (code "88") (name "Net-(DS143-K)") (class "Default")
      (node (ref "DS143") (pin "2") (pinfunction "K_2") (pintype "passive"))
      (node (ref "DS144") (pin "1") (pinfunction "A_1") (pintype "passive"))
    )
    (net (code "89") (name "Net-(DS144-K)") (class "Default")
      (node (ref "DS144") (pin "2") (pinfunction "K_2") (pintype "passive"))
      (node (ref "R212") (pin "2") (pinfunction "2_2") (pintype "passive"))
    )
    (net (code "90") (name "Net-(DS151-K)") (class "Default")
      (node (ref "DS151") (pin "2") (pinfunction "K_2") (pintype "passive"))
      (node (ref "DS152") (pin "1") (pinfunction "A_1") (pintype "passive"))
    )
    (net (code "91") (name "Net-(DS152-K)") (class "Default")
      (node (ref "DS152") (pin "2") (pinfunction "K_2") (pintype "passive"))
      (node (ref "R222") (pin "2") (pinfunction "2_2") (pintype "passive"))
    )
    (net (code "92") (name "Net-(DS153-K)") (class "Default")
      (node (ref "DS153") (pin "2") (pinfunction "K_2") (pintype "passive"))
      (node (ref "DS154") (pin "1") (pinfunction "A_1") (pintype "passive"))
    )
    (net (code "93") (name "Net-(DS154-K)") (class "Default")
      (node (ref "DS154") (pin "2") (pinfunction "K_2") (pintype "passive"))
      (node (ref "R223") (pin "2") (pinfunction "2_2") (pintype "passive"))
    )
    (net (code "94") (name "Net-(DS155-K)") (class "Default")
      (node (ref "DS155") (pin "2") (pinfunction "K_2") (pintype "passive"))
      (node (ref "DS156") (pin "1") (pinfunction "A_1") (pintype "passive"))
    )
    (net (code "95") (name "Net-(DS156-K)") (class "Default")
      (node (ref "DS156") (pin "2") (pinfunction "K_2") (pintype "passive"))
      (node (ref "R224") (pin "2") (pinfunction "2_2") (pintype "passive"))
    )
    (net (code "96") (name "Net-(DS163-K)") (class "Default")
      (node (ref "DS163") (pin "2") (pinfunction "K_2") (pintype "passive"))
      (node (ref "DS164") (pin "1") (pinfunction "A_1") (pintype "passive"))
    )
    (net (code "97") (name "Net-(DS164-K)") (class "Default")
      (node (ref "DS164") (pin "2") (pinfunction "K_2") (pintype "passive"))
      (node (ref "R228") (pin "2") (pinfunction "2_2") (pintype "passive"))
    )
    (net (code "98") (name "Net-(DS165-K)") (class "Default")
      (node (ref "DS165") (pin "2") (pinfunction "K_2") (pintype "passive"))
      (node (ref "DS166") (pin "1") (pinfunction "A_1") (pintype "passive"))
    )
    (net (code "99") (name "Net-(DS166-K)") (class "Default")
      (node (ref "DS166") (pin "2") (pinfunction "K_2") (pintype "passive"))
      (node (ref "R229") (pin "2") (pinfunction "2_2") (pintype "passive"))
    )
    (net (code "100") (name "Net-(DS167-K)") (class "Default")
      (node (ref "DS167") (pin "2") (pinfunction "K_2") (pintype "passive"))
      (node (ref "DS168") (pin "1") (pinfunction "A_1") (pintype "passive"))
    )
    (net (code "101") (name "Net-(DS168-K)") (class "Default")
      (node (ref "DS168") (pin "2") (pinfunction "K_2") (pintype "passive"))
      (node (ref "R230") (pin "2") (pinfunction "2_2") (pintype "passive"))
    )
    (net (code "102") (name "Net-(Q25-B)") (class "Default")
      (node (ref "Q25") (pin "1") (pinfunction "B_1") (pintype "passive"))
      (node (ref "R108") (pin "2") (pinfunction "2_2") (pintype "passive"))
    )
    (net (code "103") (name "Net-(Q25-C)") (class "Default")
      (node (ref "Q25") (pin "3") (pinfunction "C_3") (pintype "passive"))
      (node (ref "R114") (pin "1") (pinfunction "1_1") (pintype "passive"))
      (node (ref "R120") (pin "1") (pinfunction "1_1") (pintype "passive"))
    )
    (net (code "104") (name "Net-(Q26-B)") (class "Default")
      (node (ref "Q26") (pin "1") (pinfunction "B_1") (pintype "passive"))
      (node (ref "R109") (pin "2") (pinfunction "2_2") (pintype "passive"))
    )
    (net (code "105") (name "Net-(Q26-C)") (class "Default")
      (node (ref "Q26") (pin "3") (pinfunction "C_3") (pintype "passive"))
      (node (ref "R115") (pin "1") (pinfunction "1_1") (pintype "passive"))
      (node (ref "R121") (pin "1") (pinfunction "1_1") (pintype "passive"))
    )
    (net (code "106") (name "Net-(Q27-B)") (class "Default")
      (node (ref "Q27") (pin "1") (pinfunction "B_1") (pintype "passive"))
      (node (ref "R110") (pin "2") (pinfunction "2_2") (pintype "passive"))
    )
    (net (code "107") (name "Net-(Q27-C)") (class "Default")
      (node (ref "Q27") (pin "3") (pinfunction "C_3") (pintype "passive"))
      (node (ref "R116") (pin "1") (pinfunction "1_1") (pintype "passive"))
      (node (ref "R122") (pin "1") (pinfunction "1_1") (pintype "passive"))
    )
    (net (code "108") (name "Net-(Q31-B)") (class "Default")
      (node (ref "Q31") (pin "1") (pinfunction "B_1") (pintype "passive"))
      (node (ref "R126") (pin "2") (pinfunction "2_2") (pintype "passive"))
    )
    (net (code "109") (name "Net-(Q31-C)") (class "Default")
      (node (ref "Q31") (pin "3") (pinfunction "C_3") (pintype "passive"))
      (node (ref "R132") (pin "1") (pinfunction "1_1") (pintype "passive"))
      (node (ref "R138") (pin "1") (pinfunction "1_1") (pintype "passive"))
    )
    (net (code "110") (name "Net-(Q32-B)") (class "Default")
      (node (ref "Q32") (pin "1") (pinfunction "B_1") (pintype "passive"))
      (node (ref "R127") (pin "2") (pinfunction "2_2") (pintype "passive"))
    )
    (net (code "111") (name "Net-(Q32-C)") (class "Default")
      (node (ref "Q32") (pin "3") (pinfunction "C_3") (pintype "passive"))
      (node (ref "R133") (pin "1") (pinfunction "1_1") (pintype "passive"))
      (node (ref "R139") (pin "1") (pinfunction "1_1") (pintype "passive"))
    )
    (net (code "112") (name "Net-(Q33-B)") (class "Default")
      (node (ref "Q33") (pin "1") (pinfunction "B_1") (pintype "passive"))
      (node (ref "R128") (pin "2") (pinfunction "2_2") (pintype "passive"))
    )
    (net (code "113") (name "Net-(Q33-C)") (class "Default")
      (node (ref "Q33") (pin "3") (pinfunction "C_3") (pintype "passive"))
      (node (ref "R134") (pin "1") (pinfunction "1_1") (pintype "passive"))
      (node (ref "R140") (pin "1") (pinfunction "1_1") (pintype "passive"))
    )
    (net (code "114") (name "Net-(Q37-B)") (class "Default")
      (node (ref "Q37") (pin "1") (pinfunction "B_1") (pintype "passive"))
      (node (ref "R144") (pin "2") (pinfunction "2_2") (pintype "passive"))
    )
    (net (code "115") (name "Net-(Q37-C)") (class "Default")
      (node (ref "Q37") (pin "3") (pinfunction "C_3") (pintype "passive"))
      (node (ref "R150") (pin "1") (pinfunction "1_1") (pintype "passive"))
      (node (ref "R156") (pin "1") (pinfunction "1_1") (pintype "passive"))
    )
    (net (code "116") (name "Net-(Q38-B)") (class "Default")
      (node (ref "Q38") (pin "1") (pinfunction "B_1") (pintype "passive"))
      (node (ref "R145") (pin "2") (pinfunction "2_2") (pintype "passive"))
    )
    (net (code "117") (name "Net-(Q38-C)") (class "Default")
      (node (ref "Q38") (pin "3") (pinfunction "C_3") (pintype "passive"))
      (node (ref "R151") (pin "1") (pinfunction "1_1") (pintype "passive"))
      (node (ref "R157") (pin "1") (pinfunction "1_1") (pintype "passive"))
    )
    (net (code "118") (name "Net-(Q39-B)") (class "Default")
      (node (ref "Q39") (pin "1") (pinfunction "B_1") (pintype "passive"))
      (node (ref "R146") (pin "2") (pinfunction "2_2") (pintype "passive"))
    )
    (net (code "119") (name "Net-(Q39-C)") (class "Default")
      (node (ref "Q39") (pin "3") (pinfunction "C_3") (pintype "passive"))
      (node (ref "R152") (pin "1") (pinfunction "1_1") (pintype "passive"))
      (node (ref "R158") (pin "1") (pinfunction "1_1") (pintype "passive"))
    )
    (net (code "120") (name "Net-(Q43-B)") (class "Default")
      (node (ref "Q43") (pin "1") (pinfunction "B_1") (pintype "passive"))
      (node (ref "R162") (pin "2") (pinfunction "2_2") (pintype "passive"))
    )
    (net (code "121") (name "Net-(Q43-C)") (class "Default")
      (node (ref "Q43") (pin "3") (pinfunction "C_3") (pintype "passive"))
      (node (ref "R168") (pin "1") (pinfunction "1_1") (pintype "passive"))
      (node (ref "R174") (pin "1") (pinfunction "1_1") (pintype "passive"))
    )
    (net (code "122") (name "Net-(Q44-B)") (class "Default")
      (node (ref "Q44") (pin "1") (pinfunction "B_1") (pintype "passive"))
      (node (ref "R163") (pin "2") (pinfunction "2_2") (pintype "passive"))
    )
    (net (code "123") (name "Net-(Q44-C)") (class "Default")
      (node (ref "Q44") (pin "3") (pinfunction "C_3") (pintype "passive"))
      (node (ref "R169") (pin "1") (pinfunction "1_1") (pintype "passive"))
      (node (ref "R175") (pin "1") (pinfunction "1_1") (pintype "passive"))
    )
    (net (code "124") (name "Net-(Q45-B)") (class "Default")
      (node (ref "Q45") (pin "1") (pinfunction "B_1") (pintype "passive"))
      (node (ref "R164") (pin "2") (pinfunction "2_2") (pintype "passive"))
    )
    (net (code "125") (name "Net-(Q45-C)") (class "Default")
      (node (ref "Q45") (pin "3") (pinfunction "C_3") (pintype "passive"))
      (node (ref "R170") (pin "1") (pinfunction "1_1") (pintype "passive"))
      (node (ref "R176") (pin "1") (pinfunction "1_1") (pintype "passive"))
    )
    (net (code "126") (name "Net-(Q49-B)") (class "Default")
      (node (ref "Q49") (pin "1") (pinfunction "B_1") (pintype "passive"))
      (node (ref "R180") (pin "2") (pinfunction "2_2") (pintype "passive"))
    )
    (net (code "127") (name "Net-(Q49-C)") (class "Default")
      (node (ref "Q49") (pin "3") (pinfunction "C_3") (pintype "passive"))
      (node (ref "R186") (pin "1") (pinfunction "1_1") (pintype "passive"))
      (node (ref "R192") (pin "1") (pinfunction "1_1") (pintype "passive"))
    )
    (net (code "128") (name "Net-(Q50-B)") (class "Default")
      (node (ref "Q50") (pin "1") (pinfunction "B_1") (pintype "passive"))
      (node (ref "R181") (pin "2") (pinfunction "2_2") (pintype "passive"))
    )
    (net (code "129") (name "Net-(Q50-C)") (class "Default")
      (node (ref "Q50") (pin "3") (pinfunction "C_3") (pintype "passive"))
      (node (ref "R187") (pin "1") (pinfunction "1_1") (pintype "passive"))
      (node (ref "R193") (pin "1") (pinfunction "1_1") (pintype "passive"))
    )
    (net (code "130") (name "Net-(Q51-B)") (class "Default")
      (node (ref "Q51") (pin "1") (pinfunction "B_1") (pintype "passive"))
      (node (ref "R182") (pin "2") (pinfunction "2_2") (pintype "passive"))
    )
    (net (code "131") (name "Net-(Q51-C)") (class "Default")
      (node (ref "Q51") (pin "3") (pinfunction "C_3") (pintype "passive"))
      (node (ref "R188") (pin "1") (pinfunction "1_1") (pintype "passive"))
      (node (ref "R194") (pin "1") (pinfunction "1_1") (pintype "passive"))
    )
    (net (code "132") (name "Net-(Q55-B)") (class "Default")
      (node (ref "Q55") (pin "1") (pinfunction "B_1") (pintype "passive"))
      (node (ref "R198") (pin "2") (pinfunction "2_2") (pintype "passive"))
    )
    (net (code "133") (name "Net-(Q55-C)") (class "Default")
      (node (ref "Q55") (pin "3") (pinfunction "C_3") (pintype "passive"))
      (node (ref "R204") (pin "1") (pinfunction "1_1") (pintype "passive"))
      (node (ref "R210") (pin "1") (pinfunction "1_1") (pintype "passive"))
    )
    (net (code "134") (name "Net-(Q56-B)") (class "Default")
      (node (ref "Q56") (pin "1") (pinfunction "B_1") (pintype "passive"))
      (node (ref "R199") (pin "2") (pinfunction "2_2") (pintype "passive"))
    )
    (net (code "135") (name "Net-(Q56-C)") (class "Default")
      (node (ref "Q56") (pin "3") (pinfunction "C_3") (pintype "passive"))
      (node (ref "R205") (pin "1") (pinfunction "1_1") (pintype "passive"))
      (node (ref "R211") (pin "1") (pinfunction "1_1") (pintype "passive"))
    )
    (net (code "136") (name "Net-(Q57-B)") (class "Default")
      (node (ref "Q57") (pin "1") (pinfunction "B_1") (pintype "passive"))
      (node (ref "R200") (pin "2") (pinfunction "2_2") (pintype "passive"))
    )
    (net (code "137") (name "Net-(Q57-C)") (class "Default")
      (node (ref "Q57") (pin "3") (pinfunction "C_3") (pintype "passive"))
      (node (ref "R206") (pin "1") (pinfunction "1_1") (pintype "passive"))
      (node (ref "R212") (pin "1") (pinfunction "1_1") (pintype "passive"))
    )
    (net (code "138") (name "Net-(Q61-B)") (class "Default")
      (node (ref "Q61") (pin "1") (pinfunction "B_1") (pintype "passive"))
      (node (ref "R216") (pin "2") (pinfunction "2_2") (pintype "passive"))
    )
    (net (code "139") (name "Net-(Q61-C)") (class "Default")
      (node (ref "Q61") (pin "3") (pinfunction "C_3") (pintype "passive"))
      (node (ref "R222") (pin "1") (pinfunction "1_1") (pintype "passive"))
      (node (ref "R228") (pin "1") (pinfunction "1_1") (pintype "passive"))
    )
    (net (code "140") (name "Net-(Q62-B)") (class "Default")
      (node (ref "Q62") (pin "1") (pinfunction "B_1") (pintype "passive"))
      (node (ref "R217") (pin "2") (pinfunction "2_2") (pintype "passive"))
    )
    (net (code "141") (name "Net-(Q62-C)") (class "Default")
      (node (ref "Q62") (pin "3") (pinfunction "C_3") (pintype "passive"))
      (node (ref "R223") (pin "1") (pinfunction "1_1") (pintype "passive"))
      (node (ref "R229") (pin "1") (pinfunction "1_1") (pintype "passive"))
    )
    (net (code "142") (name "Net-(Q63-B)") (class "Default")
      (node (ref "Q63") (pin "1") (pinfunction "B_1") (pintype "passive"))
      (node (ref "R218") (pin "2") (pinfunction "2_2") (pintype "passive"))
    )
    (net (code "143") (name "Net-(Q63-C)") (class "Default")
      (node (ref "Q63") (pin "3") (pinfunction "C_3") (pintype "passive"))
      (node (ref "R224") (pin "1") (pinfunction "1_1") (pintype "passive"))
      (node (ref "R230") (pin "1") (pinfunction "1_1") (pintype "passive"))
    )
    (net (code "144") (name "Net-(U22-Q1)") (class "Default")
      (node (ref "R108") (pin "1") (pinfunction "1_1") (pintype "passive"))
      (node (ref "U22") (pin "19") (pinfunction "Q1_19") (pintype "tri_state"))
    )
    (net (code "145") (name "Net-(U22-Q2)") (class "Default")
      (node (ref "R126") (pin "1") (pinfunction "1_1") (pintype "passive"))
      (node (ref "U22") (pin "18") (pinfunction "Q2_18") (pintype "tri_state"))
    )
    (net (code "146") (name "Net-(U22-Q3)") (class "Default")
      (node (ref "R144") (pin "1") (pinfunction "1_1") (pintype "passive"))
      (node (ref "U22") (pin "17") (pinfunction "Q3_17") (pintype "tri_state"))
    )
    (net (code "147") (name "Net-(U22-Q4)") (class "Default")
      (node (ref "R162") (pin "1") (pinfunction "1_1") (pintype "passive"))
      (node (ref "U22") (pin "16") (pinfunction "Q4_16") (pintype "tri_state"))
    )
    (net (code "148") (name "Net-(U22-Q5)") (class "Default")
      (node (ref "R180") (pin "1") (pinfunction "1_1") (pintype "passive"))
      (node (ref "U22") (pin "15") (pinfunction "Q5_15") (pintype "tri_state"))
    )
    (net (code "149") (name "Net-(U22-Q6)") (class "Default")
      (node (ref "R198") (pin "1") (pinfunction "1_1") (pintype "passive"))
      (node (ref "U22") (pin "14") (pinfunction "Q6_14") (pintype "tri_state"))
    )
    (net (code "150") (name "Net-(U22-Q7)") (class "Default")
      (node (ref "R216") (pin "1") (pinfunction "1_1") (pintype "passive"))
      (node (ref "U22") (pin "13") (pinfunction "Q7_13") (pintype "tri_state"))
    )
    (net (code "151") (name "Net-(U23-Q1)") (class "Default")
      (node (ref "R109") (pin "1") (pinfunction "1_1") (pintype "passive"))
      (node (ref "U23") (pin "19") (pinfunction "Q1_19") (pintype "tri_state"))
    )
    (net (code "152") (name "Net-(U23-Q2)") (class "Default")
      (node (ref "R127") (pin "1") (pinfunction "1_1") (pintype "passive"))
      (node (ref "U23") (pin "18") (pinfunction "Q2_18") (pintype "tri_state"))
    )
    (net (code "153") (name "Net-(U23-Q3)") (class "Default")
      (node (ref "R145") (pin "1") (pinfunction "1_1") (pintype "passive"))
      (node (ref "U23") (pin "17") (pinfunction "Q3_17") (pintype "tri_state"))
    )
    (net (code "154") (name "Net-(U23-Q4)") (class "Default")
      (node (ref "R163") (pin "1") (pinfunction "1_1") (pintype "passive"))
      (node (ref "U23") (pin "16") (pinfunction "Q4_16") (pintype "tri_state"))
    )
    (net (code "155") (name "Net-(U23-Q5)") (class "Default")
      (node (ref "R181") (pin "1") (pinfunction "1_1") (pintype "passive"))
      (node (ref "U23") (pin "15") (pinfunction "Q5_15") (pintype "tri_state"))
    )
    (net (code "156") (name "Net-(U23-Q6)") (class "Default")
      (node (ref "R199") (pin "1") (pinfunction "1_1") (pintype "passive"))
      (node (ref "U23") (pin "14") (pinfunction "Q6_14") (pintype "tri_state"))
    )
    (net (code "157") (name "Net-(U23-Q7)") (class "Default")
      (node (ref "R217") (pin "1") (pinfunction "1_1") (pintype "passive"))
      (node (ref "U23") (pin "13") (pinfunction "Q7_13") (pintype "tri_state"))
    )
    (net (code "158") (name "Net-(U24-Q1)") (class "Default")
      (node (ref "R110") (pin "1") (pinfunction "1_1") (pintype "passive"))
      (node (ref "U24") (pin "19") (pinfunction "Q1_19") (pintype "tri_state"))
    )
    (net (code "159") (name "Net-(U24-Q2)") (class "Default")
      (node (ref "R128") (pin "1") (pinfunction "1_1") (pintype "passive"))
      (node (ref "U24") (pin "18") (pinfunction "Q2_18") (pintype "tri_state"))
    )
    (net (code "160") (name "Net-(U24-Q3)") (class "Default")
      (node (ref "R146") (pin "1") (pinfunction "1_1") (pintype "passive"))
      (node (ref "U24") (pin "17") (pinfunction "Q3_17") (pintype "tri_state"))
    )
    (net (code "161") (name "Net-(U24-Q4)") (class "Default")
      (node (ref "R164") (pin "1") (pinfunction "1_1") (pintype "passive"))
      (node (ref "U24") (pin "16") (pinfunction "Q4_16") (pintype "tri_state"))
    )
    (net (code "162") (name "Net-(U24-Q5)") (class "Default")
      (node (ref "R182") (pin "1") (pinfunction "1_1") (pintype "passive"))
      (node (ref "U24") (pin "15") (pinfunction "Q5_15") (pintype "tri_state"))
    )
    (net (code "163") (name "Net-(U24-Q6)") (class "Default")
      (node (ref "R200") (pin "1") (pinfunction "1_1") (pintype "passive"))
      (node (ref "U24") (pin "14") (pinfunction "Q6_14") (pintype "tri_state"))
    )
    (net (code "164") (name "Net-(U24-Q7)") (class "Default")
      (node (ref "R218") (pin "1") (pinfunction "1_1") (pintype "passive"))
      (node (ref "U24") (pin "13") (pinfunction "Q7_13") (pintype "tri_state"))
    )
    (net (code "165") (name "VCC") (class "Default")
      (node (ref "C50") (pin "1") (pinfunction "1_1") (pintype "passive"))
      (node (ref "C51") (pin "1") (pinfunction "1_1") (pintype "passive"))
      (node (ref "C52") (pin "1") (pinfunction "1_1") (pintype "passive"))
      (node (ref "U22") (pin "20") (pinfunction "VCC_20") (pintype "power_in"))
      (node (ref "U23") (pin "20") (pinfunction "VCC_20") (pintype "power_in"))
      (node (ref "U24") (pin "20") (pinfunction "VCC_20") (pintype "power_in"))
    )
  )
)
